# DC309A_TXOUT.net
KiCad netlist of a schematic drawn in Altium Designer
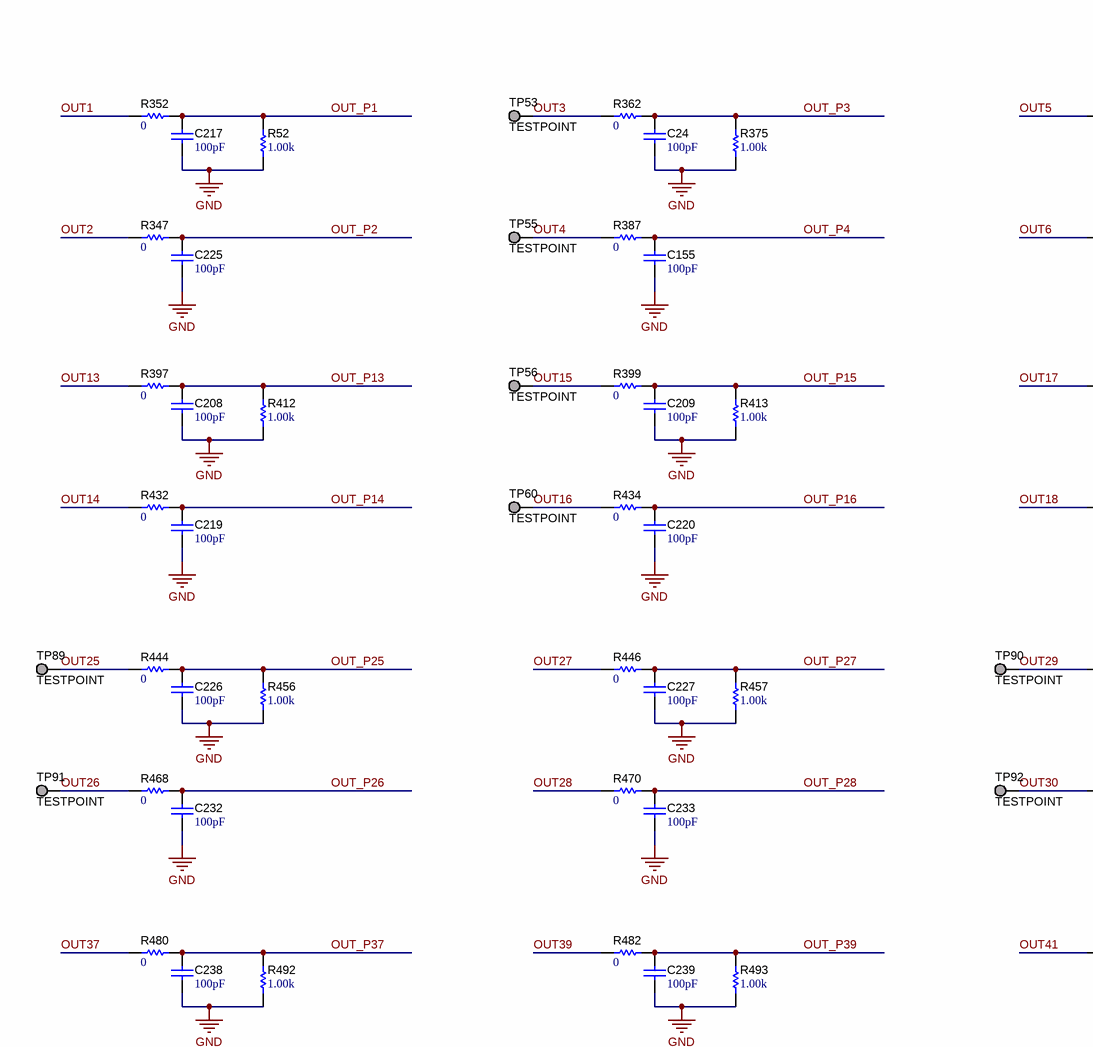
[diagram p0: DC309A_TXOUT.SchDoc, top left]
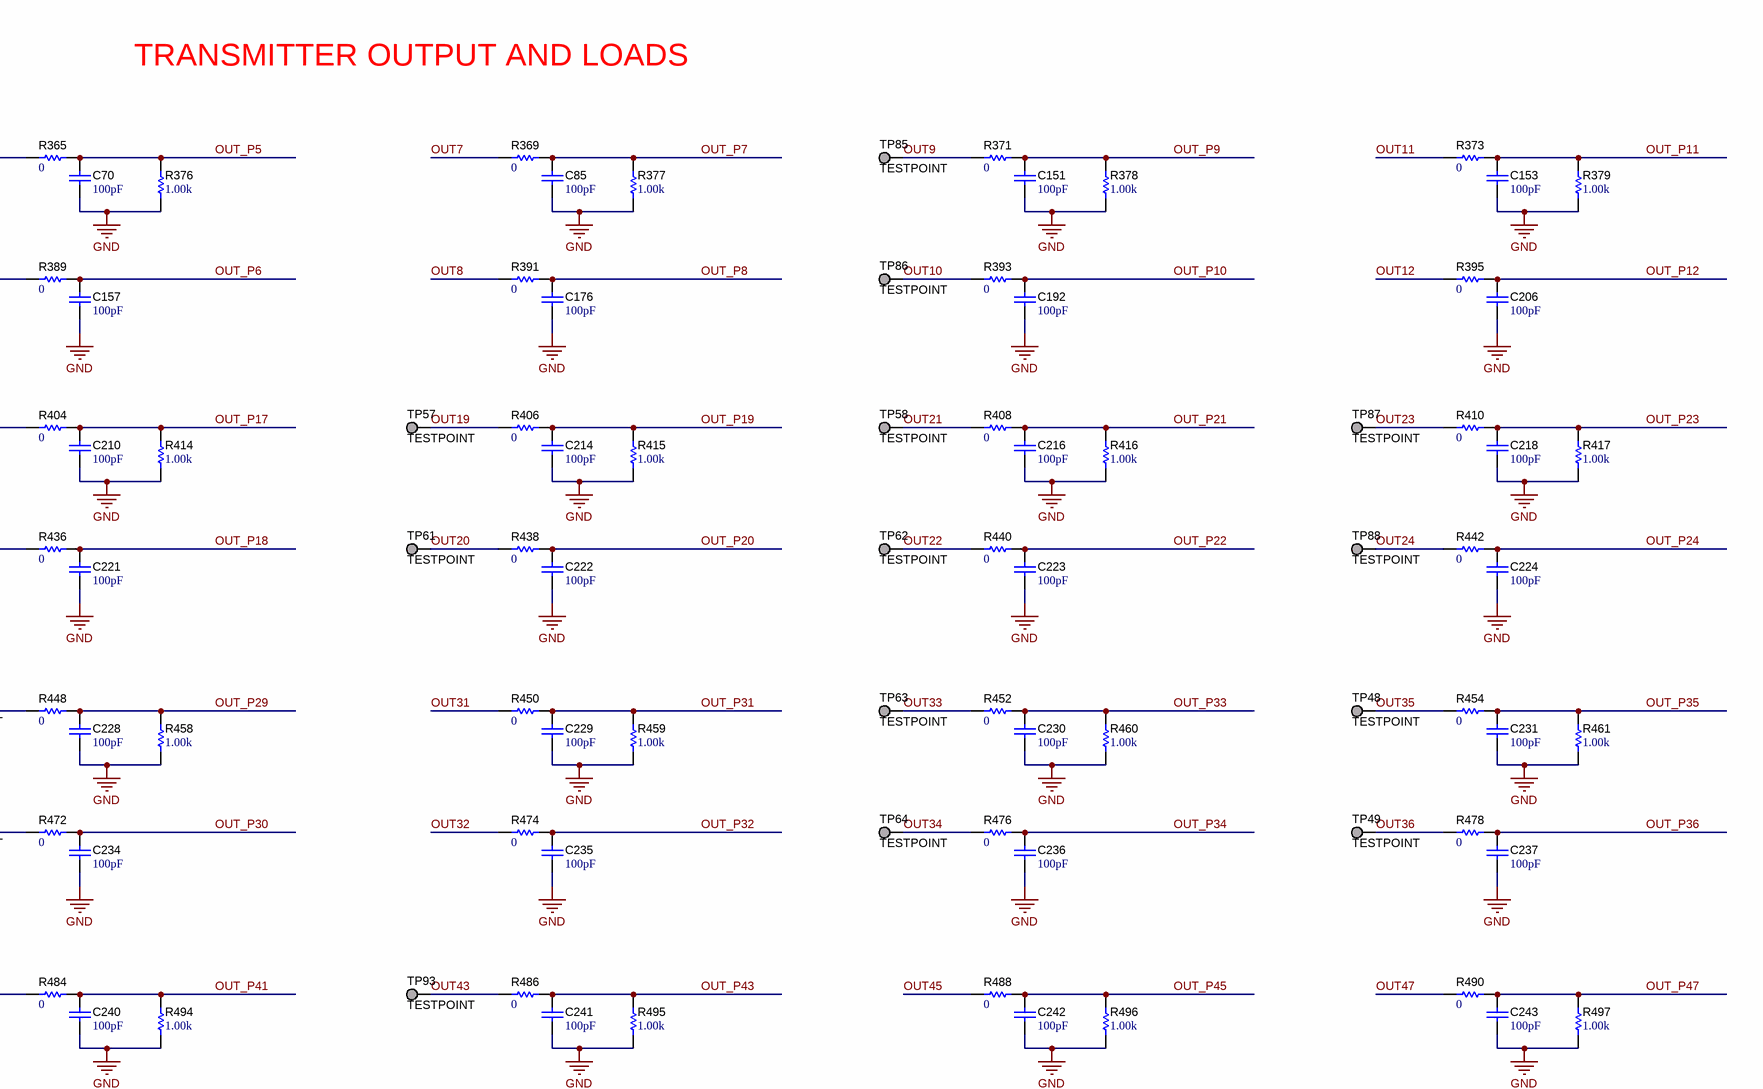
[diagram p1: DC309A_TXOUT.SchDoc, top right]
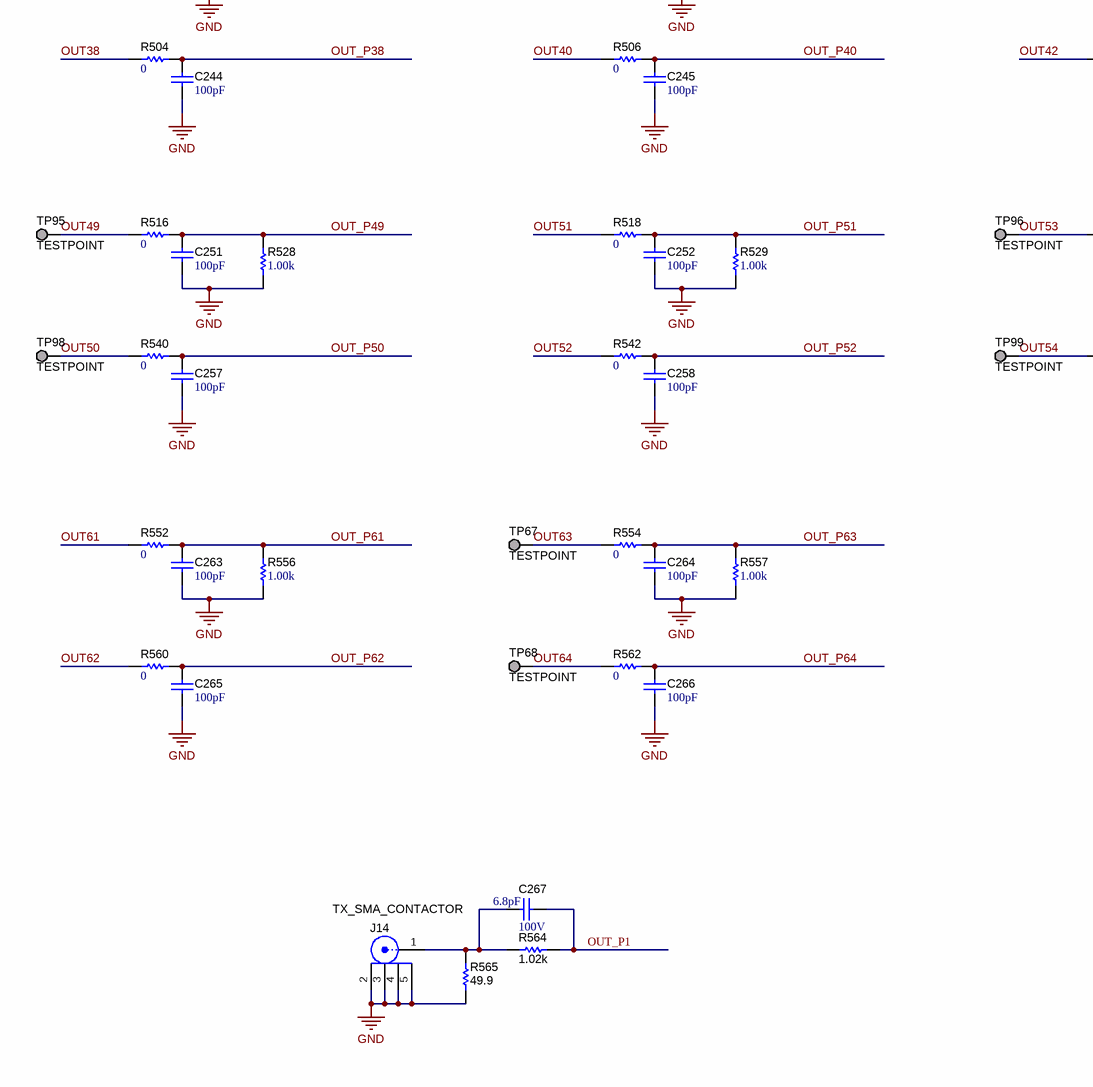
[diagram p2: DC309A_TXOUT.SchDoc, bottom left]
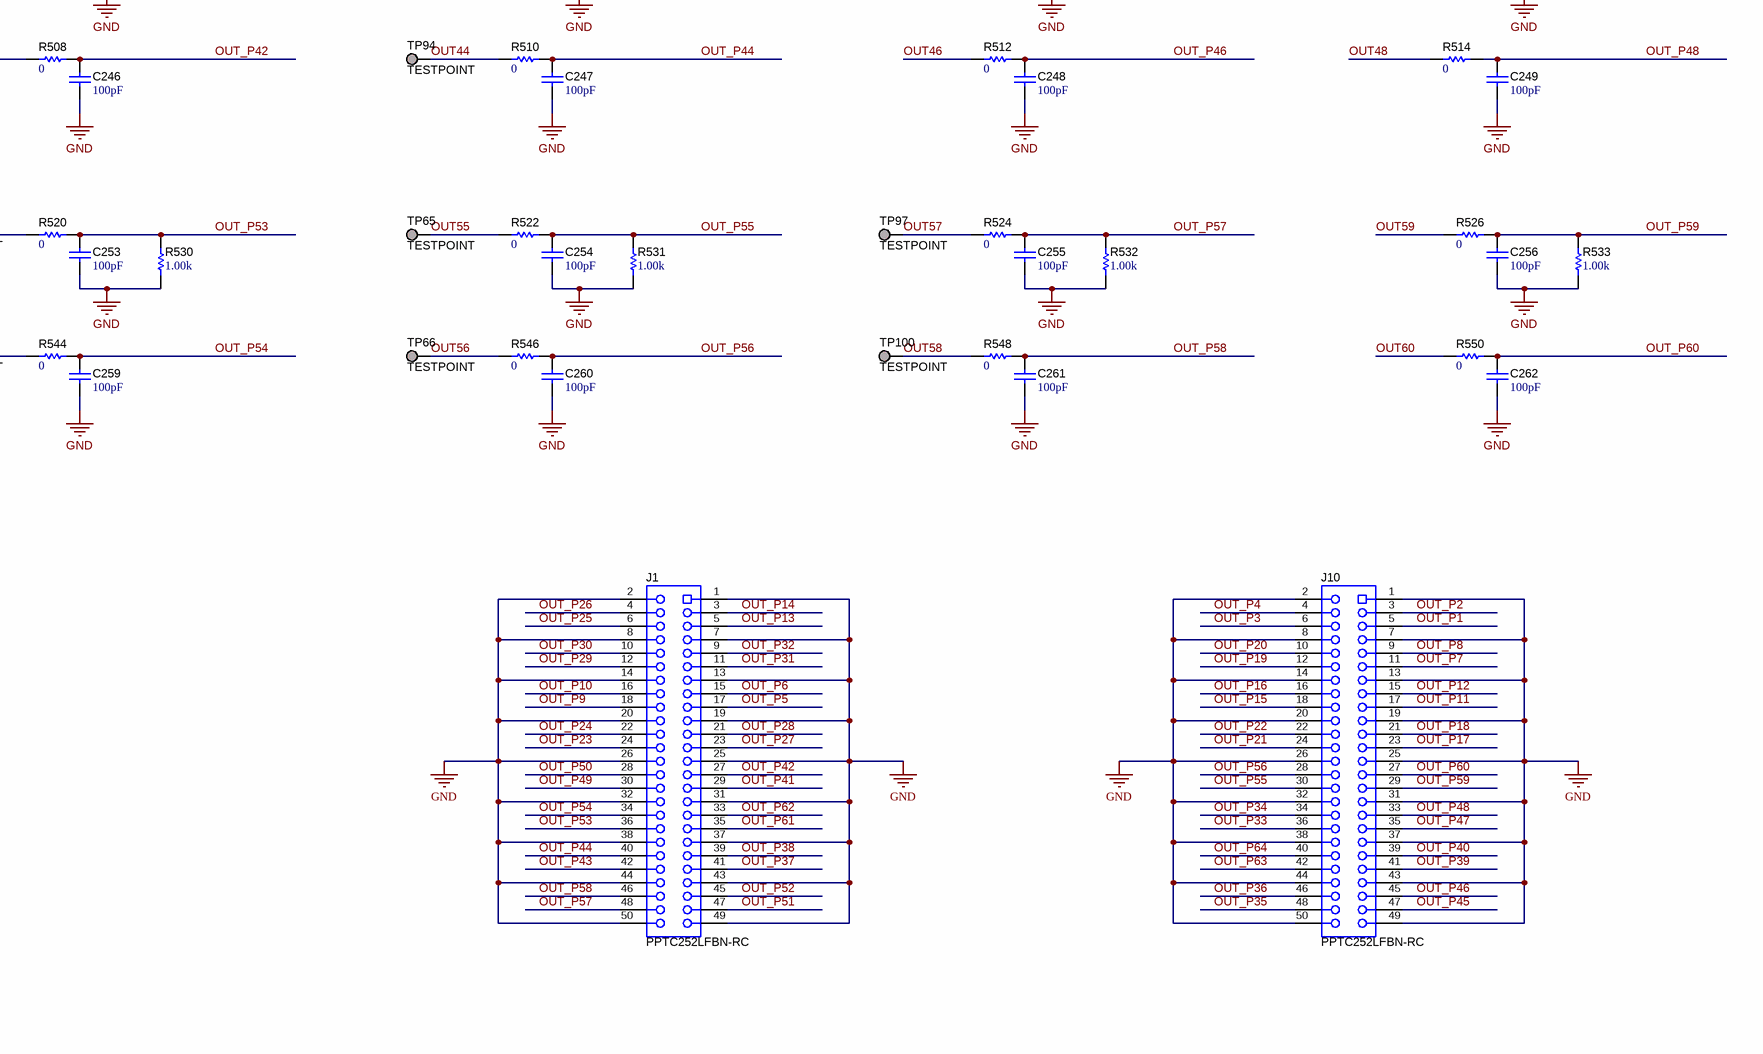
[diagram p3: DC309A_TXOUT.SchDoc, bottom right]

(export (version "E")
  (design (tool "Eeschema 10.0.6"))
  (components
    (comp (ref "C24")
      (value "AC0603JRNPOYBN101")
      (footprint "0603")
      (description "CAP, CERM, 100 pF, 250 V,+/- 5%, C0G/NP0, AEC-Q200 Grade 1, 0603")
      (fields (field (name "VALUEDISPLAYED") "100pF") (field (name "MANUFACTURER") "Yageo"))
      (libsource (lib "Altium Vault - TI") (part "Capacitor"))
    )
    (comp (ref "C70")
      (value "AC0603JRNPOYBN101")
      (footprint "0603")
      (description "CAP, CERM, 100 pF, 250 V,+/- 5%, C0G/NP0, AEC-Q200 Grade 1, 0603")
      (fields (field (name "VALUEDISPLAYED") "100pF") (field (name "MANUFACTURER") "Yageo"))
      (libsource (lib "Altium Vault - TI") (part "Capacitor"))
    )
    (comp (ref "C85")
      (value "AC0603JRNPOYBN101")
      (footprint "0603")
      (description "CAP, CERM, 100 pF, 250 V,+/- 5%, C0G/NP0, AEC-Q200 Grade 1, 0603")
      (fields (field (name "VALUEDISPLAYED") "100pF") (field (name "MANUFACTURER") "Yageo"))
      (libsource (lib "Altium Vault - TI") (part "Capacitor"))
    )
    (comp (ref "C151")
      (value "AC0603JRNPOYBN101")
      (footprint "0603")
      (description "CAP, CERM, 100 pF, 250 V,+/- 5%, C0G/NP0, AEC-Q200 Grade 1, 0603")
      (fields (field (name "VALUEDISPLAYED") "100pF") (field (name "MANUFACTURER") "Yageo"))
      (libsource (lib "Altium Vault - TI") (part "Capacitor"))
    )
    (comp (ref "C153")
      (value "AC0603JRNPOYBN101")
      (footprint "0603")
      (description "CAP, CERM, 100 pF, 250 V,+/- 5%, C0G/NP0, AEC-Q200 Grade 1, 0603")
      (fields (field (name "VALUEDISPLAYED") "100pF") (field (name "MANUFACTURER") "Yageo"))
      (libsource (lib "Altium Vault - TI") (part "Capacitor"))
    )
    (comp (ref "C155")
      (value "AC0603JRNPOYBN101")
      (footprint "0603")
      (description "CAP, CERM, 100 pF, 250 V,+/- 5%, C0G/NP0, AEC-Q200 Grade 1, 0603")
      (fields (field (name "VALUEDISPLAYED") "100pF") (field (name "MANUFACTURER") "Yageo"))
      (libsource (lib "Altium Vault - TI") (part "Capacitor"))
    )
    (comp (ref "C157")
      (value "AC0603JRNPOYBN101")
      (footprint "0603")
      (description "CAP, CERM, 100 pF, 250 V,+/- 5%, C0G/NP0, AEC-Q200 Grade 1, 0603")
      (fields (field (name "VALUEDISPLAYED") "100pF") (field (name "MANUFACTURER") "Yageo"))
      (libsource (lib "Altium Vault - TI") (part "Capacitor"))
    )
    (comp (ref "C176")
      (value "AC0603JRNPOYBN101")
      (footprint "0603")
      (description "CAP, CERM, 100 pF, 250 V,+/- 5%, C0G/NP0, AEC-Q200 Grade 1, 0603")
      (fields (field (name "VALUEDISPLAYED") "100pF") (field (name "MANUFACTURER") "Yageo"))
      (libsource (lib "Altium Vault - TI") (part "Capacitor"))
    )
    (comp (ref "C192")
      (value "AC0603JRNPOYBN101")
      (footprint "0603")
      (description "CAP, CERM, 100 pF, 250 V,+/- 5%, C0G/NP0, AEC-Q200 Grade 1, 0603")
      (fields (field (name "VALUEDISPLAYED") "100pF") (field (name "MANUFACTURER") "Yageo"))
      (libsource (lib "Altium Vault - TI") (part "Capacitor"))
    )
    (comp (ref "C206")
      (value "AC0603JRNPOYBN101")
      (footprint "0603")
      (description "CAP, CERM, 100 pF, 250 V,+/- 5%, C0G/NP0, AEC-Q200 Grade 1, 0603")
      (fields (field (name "VALUEDISPLAYED") "100pF") (field (name "MANUFACTURER") "Yageo"))
      (libsource (lib "Altium Vault - TI") (part "Capacitor"))
    )
    (comp (ref "C208")
      (value "AC0603JRNPOYBN101")
      (footprint "0603")
      (description "CAP, CERM, 100 pF, 250 V,+/- 5%, C0G/NP0, AEC-Q200 Grade 1, 0603")
      (fields (field (name "VALUEDISPLAYED") "100pF") (field (name "MANUFACTURER") "Yageo"))
      (libsource (lib "Altium Vault - TI") (part "Capacitor"))
    )
    (comp (ref "C209")
      (value "AC0603JRNPOYBN101")
      (footprint "0603")
      (description "CAP, CERM, 100 pF, 250 V,+/- 5%, C0G/NP0, AEC-Q200 Grade 1, 0603")
      (fields (field (name "VALUEDISPLAYED") "100pF") (field (name "MANUFACTURER") "Yageo"))
      (libsource (lib "Altium Vault - TI") (part "Capacitor"))
    )
    (comp (ref "C210")
      (value "AC0603JRNPOYBN101")
      (footprint "0603")
      (description "CAP, CERM, 100 pF, 250 V,+/- 5%, C0G/NP0, AEC-Q200 Grade 1, 0603")
      (fields (field (name "VALUEDISPLAYED") "100pF") (field (name "MANUFACTURER") "Yageo"))
      (libsource (lib "Altium Vault - TI") (part "Capacitor"))
    )
    (comp (ref "C214")
      (value "AC0603JRNPOYBN101")
      (footprint "0603")
      (description "CAP, CERM, 100 pF, 250 V,+/- 5%, C0G/NP0, AEC-Q200 Grade 1, 0603")
      (fields (field (name "VALUEDISPLAYED") "100pF") (field (name "MANUFACTURER") "Yageo"))
      (libsource (lib "Altium Vault - TI") (part "Capacitor"))
    )
    (comp (ref "C216")
      (value "AC0603JRNPOYBN101")
      (footprint "0603")
      (description "CAP, CERM, 100 pF, 250 V,+/- 5%, C0G/NP0, AEC-Q200 Grade 1, 0603")
      (fields (field (name "VALUEDISPLAYED") "100pF") (field (name "MANUFACTURER") "Yageo"))
      (libsource (lib "Altium Vault - TI") (part "Capacitor"))
    )
    (comp (ref "C217")
      (value "AC0603JRNPOYBN101")
      (footprint "0603")
      (description "CAP, CERM, 100 pF, 250 V,+/- 5%, C0G/NP0, AEC-Q200 Grade 1, 0603")
      (fields (field (name "VALUEDISPLAYED") "100pF") (field (name "MANUFACTURER") "Yageo"))
      (libsource (lib "Altium Vault - TI") (part "Capacitor"))
    )
    (comp (ref "C218")
      (value "AC0603JRNPOYBN101")
      (footprint "0603")
      (description "CAP, CERM, 100 pF, 250 V,+/- 5%, C0G/NP0, AEC-Q200 Grade 1, 0603")
      (fields (field (name "VALUEDISPLAYED") "100pF") (field (name "MANUFACTURER") "Yageo"))
      (libsource (lib "Altium Vault - TI") (part "Capacitor"))
    )
    (comp (ref "C219")
      (value "AC0603JRNPOYBN101")
      (footprint "0603")
      (description "CAP, CERM, 100 pF, 250 V,+/- 5%, C0G/NP0, AEC-Q200 Grade 1, 0603")
      (fields (field (name "VALUEDISPLAYED") "100pF") (field (name "MANUFACTURER") "Yageo"))
      (libsource (lib "Altium Vault - TI") (part "Capacitor"))
    )
    (comp (ref "C220")
      (value "AC0603JRNPOYBN101")
      (footprint "0603")
      (description "CAP, CERM, 100 pF, 250 V,+/- 5%, C0G/NP0, AEC-Q200 Grade 1, 0603")
      (fields (field (name "VALUEDISPLAYED") "100pF") (field (name "MANUFACTURER") "Yageo"))
      (libsource (lib "Altium Vault - TI") (part "Capacitor"))
    )
    (comp (ref "C221")
      (value "AC0603JRNPOYBN101")
      (footprint "0603")
      (description "CAP, CERM, 100 pF, 250 V,+/- 5%, C0G/NP0, AEC-Q200 Grade 1, 0603")
      (fields (field (name "VALUEDISPLAYED") "100pF") (field (name "MANUFACTURER") "Yageo"))
      (libsource (lib "Altium Vault - TI") (part "Capacitor"))
    )
    (comp (ref "C222")
      (value "AC0603JRNPOYBN101")
      (footprint "0603")
      (description "CAP, CERM, 100 pF, 250 V,+/- 5%, C0G/NP0, AEC-Q200 Grade 1, 0603")
      (fields (field (name "VALUEDISPLAYED") "100pF") (field (name "MANUFACTURER") "Yageo"))
      (libsource (lib "Altium Vault - TI") (part "Capacitor"))
    )
    (comp (ref "C223")
      (value "AC0603JRNPOYBN101")
      (footprint "0603")
      (description "CAP, CERM, 100 pF, 250 V,+/- 5%, C0G/NP0, AEC-Q200 Grade 1, 0603")
      (fields (field (name "VALUEDISPLAYED") "100pF") (field (name "MANUFACTURER") "Yageo"))
      (libsource (lib "Altium Vault - TI") (part "Capacitor"))
    )
    (comp (ref "C224")
      (value "AC0603JRNPOYBN101")
      (footprint "0603")
      (description "CAP, CERM, 100 pF, 250 V,+/- 5%, C0G/NP0, AEC-Q200 Grade 1, 0603")
      (fields (field (name "VALUEDISPLAYED") "100pF") (field (name "MANUFACTURER") "Yageo"))
      (libsource (lib "Altium Vault - TI") (part "Capacitor"))
    )
    (comp (ref "C225")
      (value "AC0603JRNPOYBN101")
      (footprint "0603")
      (description "CAP, CERM, 100 pF, 250 V,+/- 5%, C0G/NP0, AEC-Q200 Grade 1, 0603")
      (fields (field (name "VALUEDISPLAYED") "100pF") (field (name "MANUFACTURER") "Yageo"))
      (libsource (lib "Altium Vault - TI") (part "Capacitor"))
    )
    (comp (ref "C226")
      (value "AC0603JRNPOYBN101")
      (footprint "0603")
      (description "CAP, CERM, 100 pF, 250 V,+/- 5%, C0G/NP0, AEC-Q200 Grade 1, 0603")
      (fields (field (name "VALUEDISPLAYED") "100pF") (field (name "MANUFACTURER") "Yageo"))
      (libsource (lib "Altium Vault - TI") (part "Capacitor"))
    )
    (comp (ref "C227")
      (value "AC0603JRNPOYBN101")
      (footprint "0603")
      (description "CAP, CERM, 100 pF, 250 V,+/- 5%, C0G/NP0, AEC-Q200 Grade 1, 0603")
      (fields (field (name "VALUEDISPLAYED") "100pF") (field (name "MANUFACTURER") "Yageo"))
      (libsource (lib "Altium Vault - TI") (part "Capacitor"))
    )
    (comp (ref "C228")
      (value "AC0603JRNPOYBN101")
      (footprint "0603")
      (description "CAP, CERM, 100 pF, 250 V,+/- 5%, C0G/NP0, AEC-Q200 Grade 1, 0603")
      (fields (field (name "VALUEDISPLAYED") "100pF") (field (name "MANUFACTURER") "Yageo"))
      (libsource (lib "Altium Vault - TI") (part "Capacitor"))
    )
    (comp (ref "C229")
      (value "AC0603JRNPOYBN101")
      (footprint "0603")
      (description "CAP, CERM, 100 pF, 250 V,+/- 5%, C0G/NP0, AEC-Q200 Grade 1, 0603")
      (fields (field (name "VALUEDISPLAYED") "100pF") (field (name "MANUFACTURER") "Yageo"))
      (libsource (lib "Altium Vault - TI") (part "Capacitor"))
    )
    (comp (ref "C230")
      (value "AC0603JRNPOYBN101")
      (footprint "0603")
      (description "CAP, CERM, 100 pF, 250 V,+/- 5%, C0G/NP0, AEC-Q200 Grade 1, 0603")
      (fields (field (name "VALUEDISPLAYED") "100pF") (field (name "MANUFACTURER") "Yageo"))
      (libsource (lib "Altium Vault - TI") (part "Capacitor"))
    )
    (comp (ref "C231")
      (value "AC0603JRNPOYBN101")
      (footprint "0603")
      (description "CAP, CERM, 100 pF, 250 V,+/- 5%, C0G/NP0, AEC-Q200 Grade 1, 0603")
      (fields (field (name "VALUEDISPLAYED") "100pF") (field (name "MANUFACTURER") "Yageo"))
      (libsource (lib "Altium Vault - TI") (part "Capacitor"))
    )
    (comp (ref "C232")
      (value "AC0603JRNPOYBN101")
      (footprint "0603")
      (description "CAP, CERM, 100 pF, 250 V,+/- 5%, C0G/NP0, AEC-Q200 Grade 1, 0603")
      (fields (field (name "VALUEDISPLAYED") "100pF") (field (name "MANUFACTURER") "Yageo"))
      (libsource (lib "Altium Vault - TI") (part "Capacitor"))
    )
    (comp (ref "C233")
      (value "AC0603JRNPOYBN101")
      (footprint "0603")
      (description "CAP, CERM, 100 pF, 250 V,+/- 5%, C0G/NP0, AEC-Q200 Grade 1, 0603")
      (fields (field (name "VALUEDISPLAYED") "100pF") (field (name "MANUFACTURER") "Yageo"))
      (libsource (lib "Altium Vault - TI") (part "Capacitor"))
    )
    (comp (ref "C234")
      (value "AC0603JRNPOYBN101")
      (footprint "0603")
      (description "CAP, CERM, 100 pF, 250 V,+/- 5%, C0G/NP0, AEC-Q200 Grade 1, 0603")
      (fields (field (name "VALUEDISPLAYED") "100pF") (field (name "MANUFACTURER") "Yageo"))
      (libsource (lib "Altium Vault - TI") (part "Capacitor"))
    )
    (comp (ref "C235")
      (value "AC0603JRNPOYBN101")
      (footprint "0603")
      (description "CAP, CERM, 100 pF, 250 V,+/- 5%, C0G/NP0, AEC-Q200 Grade 1, 0603")
      (fields (field (name "VALUEDISPLAYED") "100pF") (field (name "MANUFACTURER") "Yageo"))
      (libsource (lib "Altium Vault - TI") (part "Capacitor"))
    )
    (comp (ref "C236")
      (value "AC0603JRNPOYBN101")
      (footprint "0603")
      (description "CAP, CERM, 100 pF, 250 V,+/- 5%, C0G/NP0, AEC-Q200 Grade 1, 0603")
      (fields (field (name "VALUEDISPLAYED") "100pF") (field (name "MANUFACTURER") "Yageo"))
      (libsource (lib "Altium Vault - TI") (part "Capacitor"))
    )
    (comp (ref "C237")
      (value "AC0603JRNPOYBN101")
      (footprint "0603")
      (description "CAP, CERM, 100 pF, 250 V,+/- 5%, C0G/NP0, AEC-Q200 Grade 1, 0603")
      (fields (field (name "VALUEDISPLAYED") "100pF") (field (name "MANUFACTURER") "Yageo"))
      (libsource (lib "Altium Vault - TI") (part "Capacitor"))
    )
    (comp (ref "C238")
      (value "AC0603JRNPOYBN101")
      (footprint "0603")
      (description "CAP, CERM, 100 pF, 250 V,+/- 5%, C0G/NP0, AEC-Q200 Grade 1, 0603")
      (fields (field (name "VALUEDISPLAYED") "100pF") (field (name "MANUFACTURER") "Yageo"))
      (libsource (lib "Altium Vault - TI") (part "Capacitor"))
    )
    (comp (ref "C239")
      (value "AC0603JRNPOYBN101")
      (footprint "0603")
      (description "CAP, CERM, 100 pF, 250 V,+/- 5%, C0G/NP0, AEC-Q200 Grade 1, 0603")
      (fields (field (name "VALUEDISPLAYED") "100pF") (field (name "MANUFACTURER") "Yageo"))
      (libsource (lib "Altium Vault - TI") (part "Capacitor"))
    )
    (comp (ref "C240")
      (value "AC0603JRNPOYBN101")
      (footprint "0603")
      (description "CAP, CERM, 100 pF, 250 V,+/- 5%, C0G/NP0, AEC-Q200 Grade 1, 0603")
      (fields (field (name "VALUEDISPLAYED") "100pF") (field (name "MANUFACTURER") "Yageo"))
      (libsource (lib "Altium Vault - TI") (part "Capacitor"))
    )
    (comp (ref "C241")
      (value "AC0603JRNPOYBN101")
      (footprint "0603")
      (description "CAP, CERM, 100 pF, 250 V,+/- 5%, C0G/NP0, AEC-Q200 Grade 1, 0603")
      (fields (field (name "VALUEDISPLAYED") "100pF") (field (name "MANUFACTURER") "Yageo"))
      (libsource (lib "Altium Vault - TI") (part "Capacitor"))
    )
    (comp (ref "C242")
      (value "AC0603JRNPOYBN101")
      (footprint "0603")
      (description "CAP, CERM, 100 pF, 250 V,+/- 5%, C0G/NP0, AEC-Q200 Grade 1, 0603")
      (fields (field (name "VALUEDISPLAYED") "100pF") (field (name "MANUFACTURER") "Yageo"))
      (libsource (lib "Altium Vault - TI") (part "Capacitor"))
    )
    (comp (ref "C243")
      (value "AC0603JRNPOYBN101")
      (footprint "0603")
      (description "CAP, CERM, 100 pF, 250 V,+/- 5%, C0G/NP0, AEC-Q200 Grade 1, 0603")
      (fields (field (name "VALUEDISPLAYED") "100pF") (field (name "MANUFACTURER") "Yageo"))
      (libsource (lib "Altium Vault - TI") (part "Capacitor"))
    )
    (comp (ref "C244")
      (value "AC0603JRNPOYBN101")
      (footprint "0603")
      (description "CAP, CERM, 100 pF, 250 V,+/- 5%, C0G/NP0, AEC-Q200 Grade 1, 0603")
      (fields (field (name "VALUEDISPLAYED") "100pF") (field (name "MANUFACTURER") "Yageo"))
      (libsource (lib "Altium Vault - TI") (part "Capacitor"))
    )
    (comp (ref "C245")
      (value "AC0603JRNPOYBN101")
      (footprint "0603")
      (description "CAP, CERM, 100 pF, 250 V,+/- 5%, C0G/NP0, AEC-Q200 Grade 1, 0603")
      (fields (field (name "VALUEDISPLAYED") "100pF") (field (name "MANUFACTURER") "Yageo"))
      (libsource (lib "Altium Vault - TI") (part "Capacitor"))
    )
    (comp (ref "C246")
      (value "AC0603JRNPOYBN101")
      (footprint "0603")
      (description "CAP, CERM, 100 pF, 250 V,+/- 5%, C0G/NP0, AEC-Q200 Grade 1, 0603")
      (fields (field (name "VALUEDISPLAYED") "100pF") (field (name "MANUFACTURER") "Yageo"))
      (libsource (lib "Altium Vault - TI") (part "Capacitor"))
    )
    (comp (ref "C247")
      (value "AC0603JRNPOYBN101")
      (footprint "0603")
      (description "CAP, CERM, 100 pF, 250 V,+/- 5%, C0G/NP0, AEC-Q200 Grade 1, 0603")
      (fields (field (name "VALUEDISPLAYED") "100pF") (field (name "MANUFACTURER") "Yageo"))
      (libsource (lib "Altium Vault - TI") (part "Capacitor"))
    )
    (comp (ref "C248")
      (value "AC0603JRNPOYBN101")
      (footprint "0603")
      (description "CAP, CERM, 100 pF, 250 V,+/- 5%, C0G/NP0, AEC-Q200 Grade 1, 0603")
      (fields (field (name "VALUEDISPLAYED") "100pF") (field (name "MANUFACTURER") "Yageo"))
      (libsource (lib "Altium Vault - TI") (part "Capacitor"))
    )
    (comp (ref "C249")
      (value "AC0603JRNPOYBN101")
      (footprint "0603")
      (description "CAP, CERM, 100 pF, 250 V,+/- 5%, C0G/NP0, AEC-Q200 Grade 1, 0603")
      (fields (field (name "VALUEDISPLAYED") "100pF") (field (name "MANUFACTURER") "Yageo"))
      (libsource (lib "Altium Vault - TI") (part "Capacitor"))
    )
    (comp (ref "C251")
      (value "AC0603JRNPOYBN101")
      (footprint "0603")
      (description "CAP, CERM, 100 pF, 250 V,+/- 5%, C0G/NP0, AEC-Q200 Grade 1, 0603")
      (fields (field (name "VALUEDISPLAYED") "100pF") (field (name "MANUFACTURER") "Yageo"))
      (libsource (lib "Altium Vault - TI") (part "Capacitor"))
    )
    (comp (ref "C252")
      (value "AC0603JRNPOYBN101")
      (footprint "0603")
      (description "CAP, CERM, 100 pF, 250 V,+/- 5%, C0G/NP0, AEC-Q200 Grade 1, 0603")
      (fields (field (name "VALUEDISPLAYED") "100pF") (field (name "MANUFACTURER") "Yageo"))
      (libsource (lib "Altium Vault - TI") (part "Capacitor"))
    )
    (comp (ref "C253")
      (value "AC0603JRNPOYBN101")
      (footprint "0603")
      (description "CAP, CERM, 100 pF, 250 V,+/- 5%, C0G/NP0, AEC-Q200 Grade 1, 0603")
      (fields (field (name "VALUEDISPLAYED") "100pF") (field (name "MANUFACTURER") "Yageo"))
      (libsource (lib "Altium Vault - TI") (part "Capacitor"))
    )
    (comp (ref "C254")
      (value "AC0603JRNPOYBN101")
      (footprint "0603")
      (description "CAP, CERM, 100 pF, 250 V,+/- 5%, C0G/NP0, AEC-Q200 Grade 1, 0603")
      (fields (field (name "VALUEDISPLAYED") "100pF") (field (name "MANUFACTURER") "Yageo"))
      (libsource (lib "Altium Vault - TI") (part "Capacitor"))
    )
    (comp (ref "C255")
      (value "AC0603JRNPOYBN101")
      (footprint "0603")
      (description "CAP, CERM, 100 pF, 250 V,+/- 5%, C0G/NP0, AEC-Q200 Grade 1, 0603")
      (fields (field (name "VALUEDISPLAYED") "100pF") (field (name "MANUFACTURER") "Yageo"))
      (libsource (lib "Altium Vault - TI") (part "Capacitor"))
    )
    (comp (ref "C256")
      (value "AC0603JRNPOYBN101")
      (footprint "0603")
      (description "CAP, CERM, 100 pF, 250 V,+/- 5%, C0G/NP0, AEC-Q200 Grade 1, 0603")
      (fields (field (name "VALUEDISPLAYED") "100pF") (field (name "MANUFACTURER") "Yageo"))
      (libsource (lib "Altium Vault - TI") (part "Capacitor"))
    )
    (comp (ref "C257")
      (value "AC0603JRNPOYBN101")
      (footprint "0603")
      (description "CAP, CERM, 100 pF, 250 V,+/- 5%, C0G/NP0, AEC-Q200 Grade 1, 0603")
      (fields (field (name "VALUEDISPLAYED") "100pF") (field (name "MANUFACTURER") "Yageo"))
      (libsource (lib "Altium Vault - TI") (part "Capacitor"))
    )
    (comp (ref "C258")
      (value "AC0603JRNPOYBN101")
      (footprint "0603")
      (description "CAP, CERM, 100 pF, 250 V,+/- 5%, C0G/NP0, AEC-Q200 Grade 1, 0603")
      (fields (field (name "VALUEDISPLAYED") "100pF") (field (name "MANUFACTURER") "Yageo"))
      (libsource (lib "Altium Vault - TI") (part "Capacitor"))
    )
    (comp (ref "C259")
      (value "AC0603JRNPOYBN101")
      (footprint "0603")
      (description "CAP, CERM, 100 pF, 250 V,+/- 5%, C0G/NP0, AEC-Q200 Grade 1, 0603")
      (fields (field (name "VALUEDISPLAYED") "100pF") (field (name "MANUFACTURER") "Yageo"))
      (libsource (lib "Altium Vault - TI") (part "Capacitor"))
    )
    (comp (ref "C260")
      (value "AC0603JRNPOYBN101")
      (footprint "0603")
      (description "CAP, CERM, 100 pF, 250 V,+/- 5%, C0G/NP0, AEC-Q200 Grade 1, 0603")
      (fields (field (name "VALUEDISPLAYED") "100pF") (field (name "MANUFACTURER") "Yageo"))
      (libsource (lib "Altium Vault - TI") (part "Capacitor"))
    )
    (comp (ref "C261")
      (value "AC0603JRNPOYBN101")
      (footprint "0603")
      (description "CAP, CERM, 100 pF, 250 V,+/- 5%, C0G/NP0, AEC-Q200 Grade 1, 0603")
      (fields (field (name "VALUEDISPLAYED") "100pF") (field (name "MANUFACTURER") "Yageo"))
      (libsource (lib "Altium Vault - TI") (part "Capacitor"))
    )
    (comp (ref "C262")
      (value "AC0603JRNPOYBN101")
      (footprint "0603")
      (description "CAP, CERM, 100 pF, 250 V,+/- 5%, C0G/NP0, AEC-Q200 Grade 1, 0603")
      (fields (field (name "VALUEDISPLAYED") "100pF") (field (name "MANUFACTURER") "Yageo"))
      (libsource (lib "Altium Vault - TI") (part "Capacitor"))
    )
    (comp (ref "C263")
      (value "AC0603JRNPOYBN101")
      (footprint "0603")
      (description "CAP, CERM, 100 pF, 250 V,+/- 5%, C0G/NP0, AEC-Q200 Grade 1, 0603")
      (fields (field (name "VALUEDISPLAYED") "100pF") (field (name "MANUFACTURER") "Yageo"))
      (libsource (lib "Altium Vault - TI") (part "Capacitor"))
    )
    (comp (ref "C264")
      (value "AC0603JRNPOYBN101")
      (footprint "0603")
      (description "CAP, CERM, 100 pF, 250 V,+/- 5%, C0G/NP0, AEC-Q200 Grade 1, 0603")
      (fields (field (name "VALUEDISPLAYED") "100pF") (field (name "MANUFACTURER") "Yageo"))
      (libsource (lib "Altium Vault - TI") (part "Capacitor"))
    )
    (comp (ref "C265")
      (value "AC0603JRNPOYBN101")
      (footprint "0603")
      (description "CAP, CERM, 100 pF, 250 V,+/- 5%, C0G/NP0, AEC-Q200 Grade 1, 0603")
      (fields (field (name "VALUEDISPLAYED") "100pF") (field (name "MANUFACTURER") "Yageo"))
      (libsource (lib "Altium Vault - TI") (part "Capacitor"))
    )
    (comp (ref "C266")
      (value "AC0603JRNPOYBN101")
      (footprint "0603")
      (description "CAP, CERM, 100 pF, 250 V,+/- 5%, C0G/NP0, AEC-Q200 Grade 1, 0603")
      (fields (field (name "VALUEDISPLAYED") "100pF") (field (name "MANUFACTURER") "Yageo"))
      (libsource (lib "Altium Vault - TI") (part "Capacitor"))
    )
    (comp (ref "C267")
      (value "CC0603CRNPO0BN6R8")
      (footprint "0603")
      (description "CAP, CERM, 6.8 pF, 100 V,+/- 3.7%, C0G/NP0, 0603")
      (fields
        (field (name "MANUFACTURER") "Yageo")
        (field (name "VDC_V") "100V")
        (field (name "VALUEDISPLAYED") "6.8pF")
      )
      (libsource (lib "Altium Vault - TI") (part "Capacitor"))
    )
    (comp (ref "J1")
      (value "PPTC252LFBN-RC")
      (footprint "Sullins_xPxC252LFBN")
      (description "Receptacle, 2.54mm, 25x2, Tin, TH")
      (fields
        (field (name "MANUFACTURER") "Sullins Connector Solutions")
        (field (name "PUBLISHER") "Texas Instruments")
      )
      (libsource (lib "Altium Vault - TI") (part "Receptacle_25x2"))
    )
    (comp (ref "J10")
      (value "PPTC252LFBN-RC")
      (footprint "Sullins_xPxC252LFBN")
      (description "Receptacle, 2.54mm, 25x2, Tin, TH")
      (fields
        (field (name "MANUFACTURER") "Sullins Connector Solutions")
        (field (name "PUBLISHER") "Texas Instruments")
      )
      (libsource (lib "Altium Vault - TI") (part "Receptacle_25x2"))
    )
    (comp (ref "J14")
      (value "901-144-8RFX")
      (footprint "AMPHENOL_901-144-8RFX")
      (description "SMA Straight Jack, Gold, 50 Ohm, TH")
      (fields (field (name "MANUFACTURER") "Amphenol RF") (field (name "PUBLISHER") "Texas Instruments"))
      (libsource (lib "Altium Vault - TI") (part "SMA_Contact1_GND2345"))
    )
    (comp (ref "R52")
      (value "CRCW25121K00FKEG")
      (footprint "2512")
      (description "RES, 1.00 k, 1%, 1 W, AEC-Q200 Grade 0, 2512")
      (fields (field (name "MANUFACTURER") "Vishay-Dale") (field (name "VALUEDISPLAYED") "1.00k"))
      (libsource (lib "Altium Vault - TI") (part "Resistor"))
    )
    (comp (ref "R347")
      (value "5106")
      (footprint "5106")
      (description "RES, 0, 1%, 0.5 W, 0805")
      (fields
        (field (name "MANUFACTURER") "Keystone")
        (field (name "VALUEDISPLAYED") "0")
        (field (name "PUBLISHER") "Texas Instruments")
      )
      (libsource (lib "Altium Vault - TI") (part "Resistor"))
    )
    (comp (ref "R352")
      (value "5106")
      (footprint "5106")
      (description "RES, 0, 1%, 0.5 W, 0805")
      (fields
        (field (name "MANUFACTURER") "Keystone")
        (field (name "VALUEDISPLAYED") "0")
        (field (name "PUBLISHER") "Texas Instruments")
      )
      (libsource (lib "Altium Vault - TI") (part "Resistor"))
    )
    (comp (ref "R362")
      (value "5106")
      (footprint "5106")
      (description "RES, 0, 1%, 0.5 W, 0805")
      (fields
        (field (name "MANUFACTURER") "Keystone")
        (field (name "VALUEDISPLAYED") "0")
        (field (name "PUBLISHER") "Texas Instruments")
      )
      (libsource (lib "Altium Vault - TI") (part "Resistor"))
    )
    (comp (ref "R365")
      (value "5106")
      (footprint "5106")
      (description "RES, 0, 1%, 0.5 W, 0805")
      (fields
        (field (name "MANUFACTURER") "Keystone")
        (field (name "VALUEDISPLAYED") "0")
        (field (name "PUBLISHER") "Texas Instruments")
      )
      (libsource (lib "Altium Vault - TI") (part "Resistor"))
    )
    (comp (ref "R369")
      (value "5106")
      (footprint "5106")
      (description "RES, 0, 1%, 0.5 W, 0805")
      (fields
        (field (name "MANUFACTURER") "Keystone")
        (field (name "VALUEDISPLAYED") "0")
        (field (name "PUBLISHER") "Texas Instruments")
      )
      (libsource (lib "Altium Vault - TI") (part "Resistor"))
    )
    (comp (ref "R371")
      (value "5106")
      (footprint "5106")
      (description "RES, 0, 1%, 0.5 W, 0805")
      (fields
        (field (name "MANUFACTURER") "Keystone")
        (field (name "VALUEDISPLAYED") "0")
        (field (name "PUBLISHER") "Texas Instruments")
      )
      (libsource (lib "Altium Vault - TI") (part "Resistor"))
    )
    (comp (ref "R373")
      (value "5106")
      (footprint "5106")
      (description "RES, 0, 1%, 0.5 W, 0805")
      (fields
        (field (name "MANUFACTURER") "Keystone")
        (field (name "VALUEDISPLAYED") "0")
        (field (name "PUBLISHER") "Texas Instruments")
      )
      (libsource (lib "Altium Vault - TI") (part "Resistor"))
    )
    (comp (ref "R375")
      (value "CRCW25121K00FKEG")
      (footprint "2512")
      (description "RES, 1.00 k, 1%, 1 W, AEC-Q200 Grade 0, 2512")
      (fields (field (name "MANUFACTURER") "Vishay-Dale") (field (name "VALUEDISPLAYED") "1.00k"))
      (libsource (lib "Altium Vault - TI") (part "Resistor"))
    )
    (comp (ref "R376")
      (value "CRCW25121K00FKEG")
      (footprint "2512")
      (description "RES, 1.00 k, 1%, 1 W, AEC-Q200 Grade 0, 2512")
      (fields (field (name "MANUFACTURER") "Vishay-Dale") (field (name "VALUEDISPLAYED") "1.00k"))
      (libsource (lib "Altium Vault - TI") (part "Resistor"))
    )
    (comp (ref "R377")
      (value "CRCW25121K00FKEG")
      (footprint "2512")
      (description "RES, 1.00 k, 1%, 1 W, AEC-Q200 Grade 0, 2512")
      (fields (field (name "MANUFACTURER") "Vishay-Dale") (field (name "VALUEDISPLAYED") "1.00k"))
      (libsource (lib "Altium Vault - TI") (part "Resistor"))
    )
    (comp (ref "R378")
      (value "CRCW25121K00FKEG")
      (footprint "2512")
      (description "RES, 1.00 k, 1%, 1 W, AEC-Q200 Grade 0, 2512")
      (fields (field (name "MANUFACTURER") "Vishay-Dale") (field (name "VALUEDISPLAYED") "1.00k"))
      (libsource (lib "Altium Vault - TI") (part "Resistor"))
    )
    (comp (ref "R379")
      (value "CRCW25121K00FKEG")
      (footprint "2512")
      (description "RES, 1.00 k, 1%, 1 W, AEC-Q200 Grade 0, 2512")
      (fields (field (name "MANUFACTURER") "Vishay-Dale") (field (name "VALUEDISPLAYED") "1.00k"))
      (libsource (lib "Altium Vault - TI") (part "Resistor"))
    )
    (comp (ref "R387")
      (value "5106")
      (footprint "5106")
      (description "RES, 0, 1%, 0.5 W, 0805")
      (fields
        (field (name "MANUFACTURER") "Keystone")
        (field (name "VALUEDISPLAYED") "0")
        (field (name "PUBLISHER") "Texas Instruments")
      )
      (libsource (lib "Altium Vault - TI") (part "Resistor"))
    )
    (comp (ref "R389")
      (value "5106")
      (footprint "5106")
      (description "RES, 0, 1%, 0.5 W, 0805")
      (fields
        (field (name "MANUFACTURER") "Keystone")
        (field (name "VALUEDISPLAYED") "0")
        (field (name "PUBLISHER") "Texas Instruments")
      )
      (libsource (lib "Altium Vault - TI") (part "Resistor"))
    )
    (comp (ref "R391")
      (value "5106")
      (footprint "5106")
      (description "RES, 0, 1%, 0.5 W, 0805")
      (fields
        (field (name "MANUFACTURER") "Keystone")
        (field (name "VALUEDISPLAYED") "0")
        (field (name "PUBLISHER") "Texas Instruments")
      )
      (libsource (lib "Altium Vault - TI") (part "Resistor"))
    )
    (comp (ref "R393")
      (value "5106")
      (footprint "5106")
      (description "RES, 0, 1%, 0.5 W, 0805")
      (fields
        (field (name "MANUFACTURER") "Keystone")
        (field (name "VALUEDISPLAYED") "0")
        (field (name "PUBLISHER") "Texas Instruments")
      )
      (libsource (lib "Altium Vault - TI") (part "Resistor"))
    )
    (comp (ref "R395")
      (value "5106")
      (footprint "5106")
      (description "RES, 0, 1%, 0.5 W, 0805")
      (fields
        (field (name "MANUFACTURER") "Keystone")
        (field (name "VALUEDISPLAYED") "0")
        (field (name "PUBLISHER") "Texas Instruments")
      )
      (libsource (lib "Altium Vault - TI") (part "Resistor"))
    )
    (comp (ref "R397")
      (value "5106")
      (footprint "5106")
      (description "RES, 0, 1%, 0.5 W, 0805")
      (fields
        (field (name "MANUFACTURER") "Keystone")
        (field (name "VALUEDISPLAYED") "0")
        (field (name "PUBLISHER") "Texas Instruments")
      )
      (libsource (lib "Altium Vault - TI") (part "Resistor"))
    )
    (comp (ref "R399")
      (value "5106")
      (footprint "5106")
      (description "RES, 0, 1%, 0.5 W, 0805")
      (fields
        (field (name "MANUFACTURER") "Keystone")
        (field (name "VALUEDISPLAYED") "0")
        (field (name "PUBLISHER") "Texas Instruments")
      )
      (libsource (lib "Altium Vault - TI") (part "Resistor"))
    )
    (comp (ref "R404")
      (value "5106")
      (footprint "5106")
      (description "RES, 0, 1%, 0.5 W, 0805")
      (fields
        (field (name "MANUFACTURER") "Keystone")
        (field (name "VALUEDISPLAYED") "0")
        (field (name "PUBLISHER") "Texas Instruments")
      )
      (libsource (lib "Altium Vault - TI") (part "Resistor"))
    )
    (comp (ref "R406")
      (value "5106")
      (footprint "5106")
      (description "RES, 0, 1%, 0.5 W, 0805")
      (fields
        (field (name "MANUFACTURER") "Keystone")
        (field (name "VALUEDISPLAYED") "0")
        (field (name "PUBLISHER") "Texas Instruments")
      )
      (libsource (lib "Altium Vault - TI") (part "Resistor"))
    )
    (comp (ref "R408")
      (value "5106")
      (footprint "5106")
      (description "RES, 0, 1%, 0.5 W, 0805")
      (fields
        (field (name "MANUFACTURER") "Keystone")
        (field (name "VALUEDISPLAYED") "0")
        (field (name "PUBLISHER") "Texas Instruments")
      )
      (libsource (lib "Altium Vault - TI") (part "Resistor"))
    )
    (comp (ref "R410")
      (value "5106")
      (footprint "5106")
      (description "RES, 0, 1%, 0.5 W, 0805")
      (fields
        (field (name "MANUFACTURER") "Keystone")
        (field (name "VALUEDISPLAYED") "0")
        (field (name "PUBLISHER") "Texas Instruments")
      )
      (libsource (lib "Altium Vault - TI") (part "Resistor"))
    )
    (comp (ref "R412")
      (value "CRCW25121K00FKEG")
      (footprint "2512")
      (description "RES, 1.00 k, 1%, 1 W, AEC-Q200 Grade 0, 2512")
      (fields (field (name "MANUFACTURER") "Vishay-Dale") (field (name "VALUEDISPLAYED") "1.00k"))
      (libsource (lib "Altium Vault - TI") (part "Resistor"))
    )
    (comp (ref "R413")
      (value "CRCW25121K00FKEG")
      (footprint "2512")
      (description "RES, 1.00 k, 1%, 1 W, AEC-Q200 Grade 0, 2512")
      (fields (field (name "MANUFACTURER") "Vishay-Dale") (field (name "VALUEDISPLAYED") "1.00k"))
      (libsource (lib "Altium Vault - TI") (part "Resistor"))
    )
    (comp (ref "R414")
      (value "CRCW25121K00FKEG")
      (footprint "2512")
      (description "RES, 1.00 k, 1%, 1 W, AEC-Q200 Grade 0, 2512")
      (fields (field (name "MANUFACTURER") "Vishay-Dale") (field (name "VALUEDISPLAYED") "1.00k"))
      (libsource (lib "Altium Vault - TI") (part "Resistor"))
    )
    (comp (ref "R415")
      (value "CRCW25121K00FKEG")
      (footprint "2512")
      (description "RES, 1.00 k, 1%, 1 W, AEC-Q200 Grade 0, 2512")
      (fields (field (name "MANUFACTURER") "Vishay-Dale") (field (name "VALUEDISPLAYED") "1.00k"))
      (libsource (lib "Altium Vault - TI") (part "Resistor"))
    )
    (comp (ref "R416")
      (value "CRCW25121K00FKEG")
      (footprint "2512")
      (description "RES, 1.00 k, 1%, 1 W, AEC-Q200 Grade 0, 2512")
      (fields (field (name "MANUFACTURER") "Vishay-Dale") (field (name "VALUEDISPLAYED") "1.00k"))
      (libsource (lib "Altium Vault - TI") (part "Resistor"))
    )
    (comp (ref "R417")
      (value "CRCW25121K00FKEG")
      (footprint "2512")
      (description "RES, 1.00 k, 1%, 1 W, AEC-Q200 Grade 0, 2512")
      (fields (field (name "MANUFACTURER") "Vishay-Dale") (field (name "VALUEDISPLAYED") "1.00k"))
      (libsource (lib "Altium Vault - TI") (part "Resistor"))
    )
    (comp (ref "R432")
      (value "5106")
      (footprint "5106")
      (description "RES, 0, 1%, 0.5 W, 0805")
      (fields
        (field (name "MANUFACTURER") "Keystone")
        (field (name "VALUEDISPLAYED") "0")
        (field (name "PUBLISHER") "Texas Instruments")
      )
      (libsource (lib "Altium Vault - TI") (part "Resistor"))
    )
    (comp (ref "R434")
      (value "5106")
      (footprint "5106")
      (description "RES, 0, 1%, 0.5 W, 0805")
      (fields
        (field (name "MANUFACTURER") "Keystone")
        (field (name "VALUEDISPLAYED") "0")
        (field (name "PUBLISHER") "Texas Instruments")
      )
      (libsource (lib "Altium Vault - TI") (part "Resistor"))
    )
    (comp (ref "R436")
      (value "5106")
      (footprint "5106")
      (description "RES, 0, 1%, 0.5 W, 0805")
      (fields
        (field (name "MANUFACTURER") "Keystone")
        (field (name "VALUEDISPLAYED") "0")
        (field (name "PUBLISHER") "Texas Instruments")
      )
      (libsource (lib "Altium Vault - TI") (part "Resistor"))
    )
    (comp (ref "R438")
      (value "5106")
      (footprint "5106")
      (description "RES, 0, 1%, 0.5 W, 0805")
      (fields
        (field (name "MANUFACTURER") "Keystone")
        (field (name "VALUEDISPLAYED") "0")
        (field (name "PUBLISHER") "Texas Instruments")
      )
      (libsource (lib "Altium Vault - TI") (part "Resistor"))
    )
    (comp (ref "R440")
      (value "5106")
      (footprint "5106")
      (description "RES, 0, 1%, 0.5 W, 0805")
      (fields
        (field (name "MANUFACTURER") "Keystone")
        (field (name "VALUEDISPLAYED") "0")
        (field (name "PUBLISHER") "Texas Instruments")
      )
      (libsource (lib "Altium Vault - TI") (part "Resistor"))
    )
    (comp (ref "R442")
      (value "5106")
      (footprint "5106")
      (description "RES, 0, 1%, 0.5 W, 0805")
      (fields
        (field (name "MANUFACTURER") "Keystone")
        (field (name "VALUEDISPLAYED") "0")
        (field (name "PUBLISHER") "Texas Instruments")
      )
      (libsource (lib "Altium Vault - TI") (part "Resistor"))
    )
    (comp (ref "R444")
      (value "5106")
      (footprint "5106")
      (description "RES, 0, 1%, 0.5 W, 0805")
      (fields
        (field (name "MANUFACTURER") "Keystone")
        (field (name "VALUEDISPLAYED") "0")
        (field (name "PUBLISHER") "Texas Instruments")
      )
      (libsource (lib "Altium Vault - TI") (part "Resistor"))
    )
    (comp (ref "R446")
      (value "5106")
      (footprint "5106")
      (description "RES, 0, 1%, 0.5 W, 0805")
      (fields
        (field (name "MANUFACTURER") "Keystone")
        (field (name "VALUEDISPLAYED") "0")
        (field (name "PUBLISHER") "Texas Instruments")
      )
      (libsource (lib "Altium Vault - TI") (part "Resistor"))
    )
    (comp (ref "R448")
      (value "5106")
      (footprint "5106")
      (description "RES, 0, 1%, 0.5 W, 0805")
      (fields
        (field (name "MANUFACTURER") "Keystone")
        (field (name "VALUEDISPLAYED") "0")
        (field (name "PUBLISHER") "Texas Instruments")
      )
      (libsource (lib "Altium Vault - TI") (part "Resistor"))
    )
    (comp (ref "R450")
      (value "5106")
      (footprint "5106")
      (description "RES, 0, 1%, 0.5 W, 0805")
      (fields
        (field (name "MANUFACTURER") "Keystone")
        (field (name "VALUEDISPLAYED") "0")
        (field (name "PUBLISHER") "Texas Instruments")
      )
      (libsource (lib "Altium Vault - TI") (part "Resistor"))
    )
    (comp (ref "R452")
      (value "5106")
      (footprint "5106")
      (description "RES, 0, 1%, 0.5 W, 0805")
      (fields
        (field (name "MANUFACTURER") "Keystone")
        (field (name "VALUEDISPLAYED") "0")
        (field (name "PUBLISHER") "Texas Instruments")
      )
      (libsource (lib "Altium Vault - TI") (part "Resistor"))
    )
    (comp (ref "R454")
      (value "5106")
      (footprint "5106")
      (description "RES, 0, 1%, 0.5 W, 0805")
      (fields
        (field (name "MANUFACTURER") "Keystone")
        (field (name "VALUEDISPLAYED") "0")
        (field (name "PUBLISHER") "Texas Instruments")
      )
      (libsource (lib "Altium Vault - TI") (part "Resistor"))
    )
    (comp (ref "R456")
      (value "CRCW25121K00FKEG")
      (footprint "2512")
      (description "RES, 1.00 k, 1%, 1 W, AEC-Q200 Grade 0, 2512")
      (fields (field (name "MANUFACTURER") "Vishay-Dale") (field (name "VALUEDISPLAYED") "1.00k"))
      (libsource (lib "Altium Vault - TI") (part "Resistor"))
    )
    (comp (ref "R457")
      (value "CRCW25121K00FKEG")
      (footprint "2512")
      (description "RES, 1.00 k, 1%, 1 W, AEC-Q200 Grade 0, 2512")
      (fields (field (name "MANUFACTURER") "Vishay-Dale") (field (name "VALUEDISPLAYED") "1.00k"))
      (libsource (lib "Altium Vault - TI") (part "Resistor"))
    )
    (comp (ref "R458")
      (value "CRCW25121K00FKEG")
      (footprint "2512")
      (description "RES, 1.00 k, 1%, 1 W, AEC-Q200 Grade 0, 2512")
      (fields (field (name "MANUFACTURER") "Vishay-Dale") (field (name "VALUEDISPLAYED") "1.00k"))
      (libsource (lib "Altium Vault - TI") (part "Resistor"))
    )
    (comp (ref "R459")
      (value "CRCW25121K00FKEG")
      (footprint "2512")
      (description "RES, 1.00 k, 1%, 1 W, AEC-Q200 Grade 0, 2512")
      (fields (field (name "MANUFACTURER") "Vishay-Dale") (field (name "VALUEDISPLAYED") "1.00k"))
      (libsource (lib "Altium Vault - TI") (part "Resistor"))
    )
    (comp (ref "R460")
      (value "CRCW25121K00FKEG")
      (footprint "2512")
      (description "RES, 1.00 k, 1%, 1 W, AEC-Q200 Grade 0, 2512")
      (fields (field (name "MANUFACTURER") "Vishay-Dale") (field (name "VALUEDISPLAYED") "1.00k"))
      (libsource (lib "Altium Vault - TI") (part "Resistor"))
    )
    (comp (ref "R461")
      (value "CRCW25121K00FKEG")
      (footprint "2512")
      (description "RES, 1.00 k, 1%, 1 W, AEC-Q200 Grade 0, 2512")
      (fields (field (name "MANUFACTURER") "Vishay-Dale") (field (name "VALUEDISPLAYED") "1.00k"))
      (libsource (lib "Altium Vault - TI") (part "Resistor"))
    )
    (comp (ref "R468")
      (value "5106")
      (footprint "5106")
      (description "RES, 0, 1%, 0.5 W, 0805")
      (fields
        (field (name "MANUFACTURER") "Keystone")
        (field (name "VALUEDISPLAYED") "0")
        (field (name "PUBLISHER") "Texas Instruments")
      )
      (libsource (lib "Altium Vault - TI") (part "Resistor"))
    )
    (comp (ref "R470")
      (value "5106")
      (footprint "5106")
      (description "RES, 0, 1%, 0.5 W, 0805")
      (fields
        (field (name "MANUFACTURER") "Keystone")
        (field (name "VALUEDISPLAYED") "0")
        (field (name "PUBLISHER") "Texas Instruments")
      )
      (libsource (lib "Altium Vault - TI") (part "Resistor"))
    )
    (comp (ref "R472")
      (value "5106")
      (footprint "5106")
      (description "RES, 0, 1%, 0.5 W, 0805")
      (fields
        (field (name "MANUFACTURER") "Keystone")
        (field (name "VALUEDISPLAYED") "0")
        (field (name "PUBLISHER") "Texas Instruments")
      )
      (libsource (lib "Altium Vault - TI") (part "Resistor"))
    )
    (comp (ref "R474")
      (value "5106")
      (footprint "5106")
      (description "RES, 0, 1%, 0.5 W, 0805")
      (fields
        (field (name "MANUFACTURER") "Keystone")
        (field (name "VALUEDISPLAYED") "0")
        (field (name "PUBLISHER") "Texas Instruments")
      )
      (libsource (lib "Altium Vault - TI") (part "Resistor"))
    )
    (comp (ref "R476")
      (value "5106")
      (footprint "5106")
      (description "RES, 0, 1%, 0.5 W, 0805")
      (fields
        (field (name "MANUFACTURER") "Keystone")
        (field (name "VALUEDISPLAYED") "0")
        (field (name "PUBLISHER") "Texas Instruments")
      )
      (libsource (lib "Altium Vault - TI") (part "Resistor"))
    )
    (comp (ref "R478")
      (value "5106")
      (footprint "5106")
      (description "RES, 0, 1%, 0.5 W, 0805")
      (fields
        (field (name "MANUFACTURER") "Keystone")
        (field (name "VALUEDISPLAYED") "0")
        (field (name "PUBLISHER") "Texas Instruments")
      )
      (libsource (lib "Altium Vault - TI") (part "Resistor"))
    )
    (comp (ref "R480")
      (value "5106")
      (footprint "5106")
      (description "RES, 0, 1%, 0.5 W, 0805")
      (fields
        (field (name "MANUFACTURER") "Keystone")
        (field (name "VALUEDISPLAYED") "0")
        (field (name "PUBLISHER") "Texas Instruments")
      )
      (libsource (lib "Altium Vault - TI") (part "Resistor"))
    )
    (comp (ref "R482")
      (value "5106")
      (footprint "5106")
      (description "RES, 0, 1%, 0.5 W, 0805")
      (fields
        (field (name "MANUFACTURER") "Keystone")
        (field (name "VALUEDISPLAYED") "0")
        (field (name "PUBLISHER") "Texas Instruments")
      )
      (libsource (lib "Altium Vault - TI") (part "Resistor"))
    )
    (comp (ref "R484")
      (value "5106")
      (footprint "5106")
      (description "RES, 0, 1%, 0.5 W, 0805")
      (fields
        (field (name "MANUFACTURER") "Keystone")
        (field (name "VALUEDISPLAYED") "0")
        (field (name "PUBLISHER") "Texas Instruments")
      )
      (libsource (lib "Altium Vault - TI") (part "Resistor"))
    )
    (comp (ref "R486")
      (value "5106")
      (footprint "5106")
      (description "RES, 0, 1%, 0.5 W, 0805")
      (fields
        (field (name "MANUFACTURER") "Keystone")
        (field (name "VALUEDISPLAYED") "0")
        (field (name "PUBLISHER") "Texas Instruments")
      )
      (libsource (lib "Altium Vault - TI") (part "Resistor"))
    )
    (comp (ref "R488")
      (value "5106")
      (footprint "5106")
      (description "RES, 0, 1%, 0.5 W, 0805")
      (fields
        (field (name "MANUFACTURER") "Keystone")
        (field (name "VALUEDISPLAYED") "0")
        (field (name "PUBLISHER") "Texas Instruments")
      )
      (libsource (lib "Altium Vault - TI") (part "Resistor"))
    )
    (comp (ref "R490")
      (value "5106")
      (footprint "5106")
      (description "RES, 0, 1%, 0.5 W, 0805")
      (fields
        (field (name "MANUFACTURER") "Keystone")
        (field (name "VALUEDISPLAYED") "0")
        (field (name "PUBLISHER") "Texas Instruments")
      )
      (libsource (lib "Altium Vault - TI") (part "Resistor"))
    )
    (comp (ref "R492")
      (value "CRCW25121K00FKEG")
      (footprint "2512")
      (description "RES, 1.00 k, 1%, 1 W, AEC-Q200 Grade 0, 2512")
      (fields (field (name "MANUFACTURER") "Vishay-Dale") (field (name "VALUEDISPLAYED") "1.00k"))
      (libsource (lib "Altium Vault - TI") (part "Resistor"))
    )
    (comp (ref "R493")
      (value "CRCW25121K00FKEG")
      (footprint "2512")
      (description "RES, 1.00 k, 1%, 1 W, AEC-Q200 Grade 0, 2512")
      (fields (field (name "MANUFACTURER") "Vishay-Dale") (field (name "VALUEDISPLAYED") "1.00k"))
      (libsource (lib "Altium Vault - TI") (part "Resistor"))
    )
    (comp (ref "R494")
      (value "CRCW25121K00FKEG")
      (footprint "2512")
      (description "RES, 1.00 k, 1%, 1 W, AEC-Q200 Grade 0, 2512")
      (fields (field (name "MANUFACTURER") "Vishay-Dale") (field (name "VALUEDISPLAYED") "1.00k"))
      (libsource (lib "Altium Vault - TI") (part "Resistor"))
    )
    (comp (ref "R495")
      (value "CRCW25121K00FKEG")
      (footprint "2512")
      (description "RES, 1.00 k, 1%, 1 W, AEC-Q200 Grade 0, 2512")
      (fields (field (name "MANUFACTURER") "Vishay-Dale") (field (name "VALUEDISPLAYED") "1.00k"))
      (libsource (lib "Altium Vault - TI") (part "Resistor"))
    )
    (comp (ref "R496")
      (value "CRCW25121K00FKEG")
      (footprint "2512")
      (description "RES, 1.00 k, 1%, 1 W, AEC-Q200 Grade 0, 2512")
      (fields (field (name "MANUFACTURER") "Vishay-Dale") (field (name "VALUEDISPLAYED") "1.00k"))
      (libsource (lib "Altium Vault - TI") (part "Resistor"))
    )
    (comp (ref "R497")
      (value "CRCW25121K00FKEG")
      (footprint "2512")
      (description "RES, 1.00 k, 1%, 1 W, AEC-Q200 Grade 0, 2512")
      (fields (field (name "MANUFACTURER") "Vishay-Dale") (field (name "VALUEDISPLAYED") "1.00k"))
      (libsource (lib "Altium Vault - TI") (part "Resistor"))
    )
    (comp (ref "R504")
      (value "5106")
      (footprint "5106")
      (description "RES, 0, 1%, 0.5 W, 0805")
      (fields
        (field (name "MANUFACTURER") "Keystone")
        (field (name "VALUEDISPLAYED") "0")
        (field (name "PUBLISHER") "Texas Instruments")
      )
      (libsource (lib "Altium Vault - TI") (part "Resistor"))
    )
    (comp (ref "R506")
      (value "5106")
      (footprint "5106")
      (description "RES, 0, 1%, 0.5 W, 0805")
      (fields
        (field (name "MANUFACTURER") "Keystone")
        (field (name "VALUEDISPLAYED") "0")
        (field (name "PUBLISHER") "Texas Instruments")
      )
      (libsource (lib "Altium Vault - TI") (part "Resistor"))
    )
    (comp (ref "R508")
      (value "5106")
      (footprint "5106")
      (description "RES, 0, 1%, 0.5 W, 0805")
      (fields
        (field (name "MANUFACTURER") "Keystone")
        (field (name "VALUEDISPLAYED") "0")
        (field (name "PUBLISHER") "Texas Instruments")
      )
      (libsource (lib "Altium Vault - TI") (part "Resistor"))
    )
    (comp (ref "R510")
      (value "5106")
      (footprint "5106")
      (description "RES, 0, 1%, 0.5 W, 0805")
      (fields
        (field (name "MANUFACTURER") "Keystone")
        (field (name "VALUEDISPLAYED") "0")
        (field (name "PUBLISHER") "Texas Instruments")
      )
      (libsource (lib "Altium Vault - TI") (part "Resistor"))
    )
    (comp (ref "R512")
      (value "5106")
      (footprint "5106")
      (description "RES, 0, 1%, 0.5 W, 0805")
      (fields
        (field (name "MANUFACTURER") "Keystone")
        (field (name "VALUEDISPLAYED") "0")
        (field (name "PUBLISHER") "Texas Instruments")
      )
      (libsource (lib "Altium Vault - TI") (part "Resistor"))
    )
    (comp (ref "R514")
      (value "5106")
      (footprint "5106")
      (description "RES, 0, 1%, 0.5 W, 0805")
      (fields
        (field (name "MANUFACTURER") "Keystone")
        (field (name "VALUEDISPLAYED") "0")
        (field (name "PUBLISHER") "Texas Instruments")
      )
      (libsource (lib "Altium Vault - TI") (part "Resistor"))
    )
    (comp (ref "R516")
      (value "5106")
      (footprint "5106")
      (description "RES, 0, 1%, 0.5 W, 0805")
      (fields
        (field (name "MANUFACTURER") "Keystone")
        (field (name "VALUEDISPLAYED") "0")
        (field (name "PUBLISHER") "Texas Instruments")
      )
      (libsource (lib "Altium Vault - TI") (part "Resistor"))
    )
    (comp (ref "R518")
      (value "5106")
      (footprint "5106")
      (description "RES, 0, 1%, 0.5 W, 0805")
      (fields
        (field (name "MANUFACTURER") "Keystone")
        (field (name "VALUEDISPLAYED") "0")
        (field (name "PUBLISHER") "Texas Instruments")
      )
      (libsource (lib "Altium Vault - TI") (part "Resistor"))
    )
    (comp (ref "R520")
      (value "5106")
      (footprint "5106")
      (description "RES, 0, 1%, 0.5 W, 0805")
      (fields
        (field (name "MANUFACTURER") "Keystone")
        (field (name "VALUEDISPLAYED") "0")
        (field (name "PUBLISHER") "Texas Instruments")
      )
      (libsource (lib "Altium Vault - TI") (part "Resistor"))
    )
    (comp (ref "R522")
      (value "5106")
      (footprint "5106")
      (description "RES, 0, 1%, 0.5 W, 0805")
      (fields
        (field (name "MANUFACTURER") "Keystone")
        (field (name "VALUEDISPLAYED") "0")
        (field (name "PUBLISHER") "Texas Instruments")
      )
      (libsource (lib "Altium Vault - TI") (part "Resistor"))
    )
    (comp (ref "R524")
      (value "5106")
      (footprint "5106")
      (description "RES, 0, 1%, 0.5 W, 0805")
      (fields
        (field (name "MANUFACTURER") "Keystone")
        (field (name "VALUEDISPLAYED") "0")
        (field (name "PUBLISHER") "Texas Instruments")
      )
      (libsource (lib "Altium Vault - TI") (part "Resistor"))
    )
    (comp (ref "R526")
      (value "5106")
      (footprint "5106")
      (description "RES, 0, 1%, 0.5 W, 0805")
      (fields
        (field (name "MANUFACTURER") "Keystone")
        (field (name "VALUEDISPLAYED") "0")
        (field (name "PUBLISHER") "Texas Instruments")
      )
      (libsource (lib "Altium Vault - TI") (part "Resistor"))
    )
    (comp (ref "R528")
      (value "CRCW25121K00FKEG")
      (footprint "2512")
      (description "RES, 1.00 k, 1%, 1 W, AEC-Q200 Grade 0, 2512")
      (fields (field (name "MANUFACTURER") "Vishay-Dale") (field (name "VALUEDISPLAYED") "1.00k"))
      (libsource (lib "Altium Vault - TI") (part "Resistor"))
    )
    (comp (ref "R529")
      (value "CRCW25121K00FKEG")
      (footprint "2512")
      (description "RES, 1.00 k, 1%, 1 W, AEC-Q200 Grade 0, 2512")
      (fields (field (name "MANUFACTURER") "Vishay-Dale") (field (name "VALUEDISPLAYED") "1.00k"))
      (libsource (lib "Altium Vault - TI") (part "Resistor"))
    )
    (comp (ref "R530")
      (value "CRCW25121K00FKEG")
      (footprint "2512")
      (description "RES, 1.00 k, 1%, 1 W, AEC-Q200 Grade 0, 2512")
      (fields (field (name "MANUFACTURER") "Vishay-Dale") (field (name "VALUEDISPLAYED") "1.00k"))
      (libsource (lib "Altium Vault - TI") (part "Resistor"))
    )
    (comp (ref "R531")
      (value "CRCW25121K00FKEG")
      (footprint "2512")
      (description "RES, 1.00 k, 1%, 1 W, AEC-Q200 Grade 0, 2512")
      (fields (field (name "MANUFACTURER") "Vishay-Dale") (field (name "VALUEDISPLAYED") "1.00k"))
      (libsource (lib "Altium Vault - TI") (part "Resistor"))
    )
    (comp (ref "R532")
      (value "CRCW25121K00FKEG")
      (footprint "2512")
      (description "RES, 1.00 k, 1%, 1 W, AEC-Q200 Grade 0, 2512")
      (fields (field (name "MANUFACTURER") "Vishay-Dale") (field (name "VALUEDISPLAYED") "1.00k"))
      (libsource (lib "Altium Vault - TI") (part "Resistor"))
    )
    (comp (ref "R533")
      (value "CRCW25121K00FKEG")
      (footprint "2512")
      (description "RES, 1.00 k, 1%, 1 W, AEC-Q200 Grade 0, 2512")
      (fields (field (name "MANUFACTURER") "Vishay-Dale") (field (name "VALUEDISPLAYED") "1.00k"))
      (libsource (lib "Altium Vault - TI") (part "Resistor"))
    )
    (comp (ref "R540")
      (value "5106")
      (footprint "5106")
      (description "RES, 0, 1%, 0.5 W, 0805")
      (fields
        (field (name "MANUFACTURER") "Keystone")
        (field (name "VALUEDISPLAYED") "0")
        (field (name "PUBLISHER") "Texas Instruments")
      )
      (libsource (lib "Altium Vault - TI") (part "Resistor"))
    )
    (comp (ref "R542")
      (value "5106")
      (footprint "5106")
      (description "RES, 0, 1%, 0.5 W, 0805")
      (fields
        (field (name "MANUFACTURER") "Keystone")
        (field (name "VALUEDISPLAYED") "0")
        (field (name "PUBLISHER") "Texas Instruments")
      )
      (libsource (lib "Altium Vault - TI") (part "Resistor"))
    )
    (comp (ref "R544")
      (value "5106")
      (footprint "5106")
      (description "RES, 0, 1%, 0.5 W, 0805")
      (fields
        (field (name "MANUFACTURER") "Keystone")
        (field (name "VALUEDISPLAYED") "0")
        (field (name "PUBLISHER") "Texas Instruments")
      )
      (libsource (lib "Altium Vault - TI") (part "Resistor"))
    )
    (comp (ref "R546")
      (value "5106")
      (footprint "5106")
      (description "RES, 0, 1%, 0.5 W, 0805")
      (fields
        (field (name "MANUFACTURER") "Keystone")
        (field (name "VALUEDISPLAYED") "0")
        (field (name "PUBLISHER") "Texas Instruments")
      )
      (libsource (lib "Altium Vault - TI") (part "Resistor"))
    )
    (comp (ref "R548")
      (value "5106")
      (footprint "5106")
      (description "RES, 0, 1%, 0.5 W, 0805")
      (fields
        (field (name "MANUFACTURER") "Keystone")
        (field (name "VALUEDISPLAYED") "0")
        (field (name "PUBLISHER") "Texas Instruments")
      )
      (libsource (lib "Altium Vault - TI") (part "Resistor"))
    )
    (comp (ref "R550")
      (value "5106")
      (footprint "5106")
      (description "RES, 0, 1%, 0.5 W, 0805")
      (fields
        (field (name "MANUFACTURER") "Keystone")
        (field (name "VALUEDISPLAYED") "0")
        (field (name "PUBLISHER") "Texas Instruments")
      )
      (libsource (lib "Altium Vault - TI") (part "Resistor"))
    )
    (comp (ref "R552")
      (value "5106")
      (footprint "5106")
      (description "RES, 0, 1%, 0.5 W, 0805")
      (fields
        (field (name "MANUFACTURER") "Keystone")
        (field (name "VALUEDISPLAYED") "0")
        (field (name "PUBLISHER") "Texas Instruments")
      )
      (libsource (lib "Altium Vault - TI") (part "Resistor"))
    )
    (comp (ref "R554")
      (value "5106")
      (footprint "5106")
      (description "RES, 0, 1%, 0.5 W, 0805")
      (fields
        (field (name "MANUFACTURER") "Keystone")
        (field (name "VALUEDISPLAYED") "0")
        (field (name "PUBLISHER") "Texas Instruments")
      )
      (libsource (lib "Altium Vault - TI") (part "Resistor"))
    )
    (comp (ref "R556")
      (value "CRCW25121K00FKEG")
      (footprint "2512")
      (description "RES, 1.00 k, 1%, 1 W, AEC-Q200 Grade 0, 2512")
      (fields (field (name "MANUFACTURER") "Vishay-Dale") (field (name "VALUEDISPLAYED") "1.00k"))
      (libsource (lib "Altium Vault - TI") (part "Resistor"))
    )
    (comp (ref "R557")
      (value "CRCW25121K00FKEG")
      (footprint "2512")
      (description "RES, 1.00 k, 1%, 1 W, AEC-Q200 Grade 0, 2512")
      (fields (field (name "MANUFACTURER") "Vishay-Dale") (field (name "VALUEDISPLAYED") "1.00k"))
      (libsource (lib "Altium Vault - TI") (part "Resistor"))
    )
    (comp (ref "R560")
      (value "5106")
      (footprint "5106")
      (description "RES, 0, 1%, 0.5 W, 0805")
      (fields
        (field (name "MANUFACTURER") "Keystone")
        (field (name "VALUEDISPLAYED") "0")
        (field (name "PUBLISHER") "Texas Instruments")
      )
      (libsource (lib "Altium Vault - TI") (part "Resistor"))
    )
    (comp (ref "R562")
      (value "5106")
      (footprint "5106")
      (description "RES, 0, 1%, 0.5 W, 0805")
      (fields
        (field (name "MANUFACTURER") "Keystone")
        (field (name "VALUEDISPLAYED") "0")
        (field (name "PUBLISHER") "Texas Instruments")
      )
      (libsource (lib "Altium Vault - TI") (part "Resistor"))
    )
    (comp (ref "R564")
      (value "Resistor")
      (footprint "1206")
      (description "RES, 1.02 k, 1%, 0.25 W, AEC-Q200 Grade 0, 1206")
      (fields
        (field (name "PARTNUMBER") "CRCW12061K02FKEA")
        (field (name "VALUEDISPLAYED") "1.02k")
        (field (name "MANUFACTURER") "Vishay-Dale")
      )
      (libsource (lib "Altium Vault - TI") (part "CMP-0016688-3"))
    )
    (comp (ref "R565")
      (value "TNPW060349R9BEEA")
      (footprint "TNPW0603")
      (description "RES, 49.9, 0.1%, 0.1 W, AEC-Q200 Grade 1, 0603")
      (fields
        (field (name "MANUFACTURER") "Vishay-Dale")
        (field (name "VALUEDISPLAYED") "49.9")
        (field (name "PUBLISHER") "Texas Instruments")
      )
      (libsource (lib "Altium Vault - TI") (part "Resistor"))
    )
    (comp (ref "TP48")
      (value "TESTPOINT")
      (footprint "TP_50MIL-SMT")
      (description "TEST POINT.  No entry in BOM.")
      (libsource (lib "Altium Vault - TI") (part "TESTPOINT"))
    )
    (comp (ref "TP49")
      (value "TESTPOINT")
      (footprint "TP_50MIL-SMT")
      (description "TEST POINT.  No entry in BOM.")
      (libsource (lib "Altium Vault - TI") (part "TESTPOINT"))
    )
    (comp (ref "TP53")
      (value "TESTPOINT")
      (footprint "TP_50MIL-SMT")
      (description "TEST POINT.  No entry in BOM.")
      (libsource (lib "Altium Vault - TI") (part "TESTPOINT"))
    )
    (comp (ref "TP55")
      (value "TESTPOINT")
      (footprint "TP_50MIL-SMT")
      (description "TEST POINT.  No entry in BOM.")
      (libsource (lib "Altium Vault - TI") (part "TESTPOINT"))
    )
    (comp (ref "TP56")
      (value "TESTPOINT")
      (footprint "TP_50MIL-SMT")
      (description "TEST POINT.  No entry in BOM.")
      (libsource (lib "Altium Vault - TI") (part "TESTPOINT"))
    )
    (comp (ref "TP57")
      (value "TESTPOINT")
      (footprint "TP_50MIL-SMT")
      (description "TEST POINT.  No entry in BOM.")
      (libsource (lib "Altium Vault - TI") (part "TESTPOINT"))
    )
    (comp (ref "TP58")
      (value "TESTPOINT")
      (footprint "TP_50MIL-SMT")
      (description "TEST POINT.  No entry in BOM.")
      (libsource (lib "Altium Vault - TI") (part "TESTPOINT"))
    )
    (comp (ref "TP60")
      (value "TESTPOINT")
      (footprint "TP_50MIL-SMT")
      (description "TEST POINT.  No entry in BOM.")
      (libsource (lib "Altium Vault - TI") (part "TESTPOINT"))
    )
    (comp (ref "TP61")
      (value "TESTPOINT")
      (footprint "TP_50MIL-SMT")
      (description "TEST POINT.  No entry in BOM.")
      (libsource (lib "Altium Vault - TI") (part "TESTPOINT"))
    )
    (comp (ref "TP62")
      (value "TESTPOINT")
      (footprint "TP_50MIL-SMT")
      (description "TEST POINT.  No entry in BOM.")
      (libsource (lib "Altium Vault - TI") (part "TESTPOINT"))
    )
    (comp (ref "TP63")
      (value "TESTPOINT")
      (footprint "TP_50MIL-SMT")
      (description "TEST POINT.  No entry in BOM.")
      (libsource (lib "Altium Vault - TI") (part "TESTPOINT"))
    )
    (comp (ref "TP64")
      (value "TESTPOINT")
      (footprint "TP_50MIL-SMT")
      (description "TEST POINT.  No entry in BOM.")
      (libsource (lib "Altium Vault - TI") (part "TESTPOINT"))
    )
    (comp (ref "TP65")
      (value "TESTPOINT")
      (footprint "TP_50MIL-SMT")
      (description "TEST POINT.  No entry in BOM.")
      (libsource (lib "Altium Vault - TI") (part "TESTPOINT"))
    )
    (comp (ref "TP66")
      (value "TESTPOINT")
      (footprint "TP_50MIL-SMT")
      (description "TEST POINT.  No entry in BOM.")
      (libsource (lib "Altium Vault - TI") (part "TESTPOINT"))
    )
    (comp (ref "TP67")
      (value "TESTPOINT")
      (footprint "TP_50MIL-SMT")
      (description "TEST POINT.  No entry in BOM.")
      (libsource (lib "Altium Vault - TI") (part "TESTPOINT"))
    )
    (comp (ref "TP68")
      (value "TESTPOINT")
      (footprint "TP_50MIL-SMT")
      (description "TEST POINT.  No entry in BOM.")
      (libsource (lib "Altium Vault - TI") (part "TESTPOINT"))
    )
    (comp (ref "TP85")
      (value "TESTPOINT")
      (footprint "TP_50MIL-SMT")
      (description "TEST POINT.  No entry in BOM.")
      (libsource (lib "Altium Vault - TI") (part "TESTPOINT"))
    )
    (comp (ref "TP86")
      (value "TESTPOINT")
      (footprint "TP_50MIL-SMT")
      (description "TEST POINT.  No entry in BOM.")
      (libsource (lib "Altium Vault - TI") (part "TESTPOINT"))
    )
    (comp (ref "TP87")
      (value "TESTPOINT")
      (footprint "TP_50MIL-SMT")
      (description "TEST POINT.  No entry in BOM.")
      (libsource (lib "Altium Vault - TI") (part "TESTPOINT"))
    )
    (comp (ref "TP88")
      (value "TESTPOINT")
      (footprint "TP_50MIL-SMT")
      (description "TEST POINT.  No entry in BOM.")
      (libsource (lib "Altium Vault - TI") (part "TESTPOINT"))
    )
    (comp (ref "TP89")
      (value "TESTPOINT")
      (footprint "TP_50MIL-SMT")
      (description "TEST POINT.  No entry in BOM.")
      (libsource (lib "Altium Vault - TI") (part "TESTPOINT"))
    )
    (comp (ref "TP90")
      (value "TESTPOINT")
      (footprint "TP_50MIL-SMT")
      (description "TEST POINT.  No entry in BOM.")
      (libsource (lib "Altium Vault - TI") (part "TESTPOINT"))
    )
    (comp (ref "TP91")
      (value "TESTPOINT")
      (footprint "TP_50MIL-SMT")
      (description "TEST POINT.  No entry in BOM.")
      (libsource (lib "Altium Vault - TI") (part "TESTPOINT"))
    )
    (comp (ref "TP92")
      (value "TESTPOINT")
      (footprint "TP_50MIL-SMT")
      (description "TEST POINT.  No entry in BOM.")
      (libsource (lib "Altium Vault - TI") (part "TESTPOINT"))
    )
    (comp (ref "TP93")
      (value "TESTPOINT")
      (footprint "TP_50MIL-SMT")
      (description "TEST POINT.  No entry in BOM.")
      (libsource (lib "Altium Vault - TI") (part "TESTPOINT"))
    )
    (comp (ref "TP94")
      (value "TESTPOINT")
      (footprint "TP_50MIL-SMT")
      (description "TEST POINT.  No entry in BOM.")
      (libsource (lib "Altium Vault - TI") (part "TESTPOINT"))
    )
    (comp (ref "TP95")
      (value "TESTPOINT")
      (footprint "TP_50MIL-SMT")
      (description "TEST POINT.  No entry in BOM.")
      (libsource (lib "Altium Vault - TI") (part "TESTPOINT"))
    )
    (comp (ref "TP96")
      (value "TESTPOINT")
      (footprint "TP_50MIL-SMT")
      (description "TEST POINT.  No entry in BOM.")
      (libsource (lib "Altium Vault - TI") (part "TESTPOINT"))
    )
    (comp (ref "TP97")
      (value "TESTPOINT")
      (footprint "TP_50MIL-SMT")
      (description "TEST POINT.  No entry in BOM.")
      (libsource (lib "Altium Vault - TI") (part "TESTPOINT"))
    )
    (comp (ref "TP98")
      (value "TESTPOINT")
      (footprint "TP_50MIL-SMT")
      (description "TEST POINT.  No entry in BOM.")
      (libsource (lib "Altium Vault - TI") (part "TESTPOINT"))
    )
    (comp (ref "TP99")
      (value "TESTPOINT")
      (footprint "TP_50MIL-SMT")
      (description "TEST POINT.  No entry in BOM.")
      (libsource (lib "Altium Vault - TI") (part "TESTPOINT"))
    )
    (comp (ref "TP100")
      (value "TESTPOINT")
      (footprint "TP_50MIL-SMT")
      (description "TEST POINT.  No entry in BOM.")
      (libsource (lib "Altium Vault - TI") (part "TESTPOINT"))
    )
  )
  (nets
    (net (code "1") (name "/OUT1") (class "Default")
      (node (ref "R352") (pin "1") (pinfunction "1_1") (pintype "passive"))
    )
    (net (code "2") (name "/OUT2") (class "Default")
      (node (ref "R347") (pin "1") (pinfunction "1_1") (pintype "passive"))
    )
    (net (code "3") (name "/OUT3") (class "Default")
      (node (ref "R362") (pin "1") (pinfunction "1_1") (pintype "passive"))
      (node (ref "TP53") (pin "1") (pintype "passive"))
    )
    (net (code "4") (name "/OUT4") (class "Default")
      (node (ref "R387") (pin "1") (pinfunction "1_1") (pintype "passive"))
      (node (ref "TP55") (pin "1") (pintype "passive"))
    )
    (net (code "5") (name "/OUT5") (class "Default")
      (node (ref "R365") (pin "1") (pinfunction "1_1") (pintype "passive"))
    )
    (net (code "6") (name "/OUT6") (class "Default")
      (node (ref "R389") (pin "1") (pinfunction "1_1") (pintype "passive"))
    )
    (net (code "7") (name "/OUT7") (class "Default")
      (node (ref "R369") (pin "1") (pinfunction "1_1") (pintype "passive"))
    )
    (net (code "8") (name "/OUT8") (class "Default")
      (node (ref "R391") (pin "1") (pinfunction "1_1") (pintype "passive"))
    )
    (net (code "9") (name "/OUT9") (class "Default")
      (node (ref "R371") (pin "1") (pinfunction "1_1") (pintype "passive"))
      (node (ref "TP85") (pin "1") (pintype "passive"))
    )
    (net (code "10") (name "/OUT10") (class "Default")
      (node (ref "R393") (pin "1") (pinfunction "1_1") (pintype "passive"))
      (node (ref "TP86") (pin "1") (pintype "passive"))
    )
    (net (code "11") (name "/OUT11") (class "Default")
      (node (ref "R373") (pin "1") (pinfunction "1_1") (pintype "passive"))
    )
    (net (code "12") (name "/OUT12") (class "Default")
      (node (ref "R395") (pin "1") (pinfunction "1_1") (pintype "passive"))
    )
    (net (code "13") (name "/OUT13") (class "Default")
      (node (ref "R397") (pin "1") (pinfunction "1_1") (pintype "passive"))
    )
    (net (code "14") (name "/OUT14") (class "Default")
      (node (ref "R432") (pin "1") (pinfunction "1_1") (pintype "passive"))
    )
    (net (code "15") (name "/OUT15") (class "Default")
      (node (ref "R399") (pin "1") (pinfunction "1_1") (pintype "passive"))
      (node (ref "TP56") (pin "1") (pintype "passive"))
    )
    (net (code "16") (name "/OUT16") (class "Default")
      (node (ref "R434") (pin "1") (pinfunction "1_1") (pintype "passive"))
      (node (ref "TP60") (pin "1") (pintype "passive"))
    )
    (net (code "17") (name "/OUT17") (class "Default")
      (node (ref "R404") (pin "1") (pinfunction "1_1") (pintype "passive"))
    )
    (net (code "18") (name "/OUT18") (class "Default")
      (node (ref "R436") (pin "1") (pinfunction "1_1") (pintype "passive"))
    )
    (net (code "19") (name "/OUT19") (class "Default")
      (node (ref "R406") (pin "1") (pinfunction "1_1") (pintype "passive"))
      (node (ref "TP57") (pin "1") (pintype "passive"))
    )
    (net (code "20") (name "/OUT20") (class "Default")
      (node (ref "R438") (pin "1") (pinfunction "1_1") (pintype "passive"))
      (node (ref "TP61") (pin "1") (pintype "passive"))
    )
    (net (code "21") (name "/OUT21") (class "Default")
      (node (ref "R408") (pin "1") (pinfunction "1_1") (pintype "passive"))
      (node (ref "TP58") (pin "1") (pintype "passive"))
    )
    (net (code "22") (name "/OUT22") (class "Default")
      (node (ref "R440") (pin "1") (pinfunction "1_1") (pintype "passive"))
      (node (ref "TP62") (pin "1") (pintype "passive"))
    )
    (net (code "23") (name "/OUT23") (class "Default")
      (node (ref "R410") (pin "1") (pinfunction "1_1") (pintype "passive"))
      (node (ref "TP87") (pin "1") (pintype "passive"))
    )
    (net (code "24") (name "/OUT24") (class "Default")
      (node (ref "R442") (pin "1") (pinfunction "1_1") (pintype "passive"))
      (node (ref "TP88") (pin "1") (pintype "passive"))
    )
    (net (code "25") (name "/OUT25") (class "Default")
      (node (ref "R444") (pin "1") (pinfunction "1_1") (pintype "passive"))
      (node (ref "TP89") (pin "1") (pintype "passive"))
    )
    (net (code "26") (name "/OUT26") (class "Default")
      (node (ref "R468") (pin "1") (pinfunction "1_1") (pintype "passive"))
      (node (ref "TP91") (pin "1") (pintype "passive"))
    )
    (net (code "27") (name "/OUT27") (class "Default")
      (node (ref "R446") (pin "1") (pinfunction "1_1") (pintype "passive"))
    )
    (net (code "28") (name "/OUT28") (class "Default")
      (node (ref "R470") (pin "1") (pinfunction "1_1") (pintype "passive"))
    )
    (net (code "29") (name "/OUT29") (class "Default")
      (node (ref "R448") (pin "1") (pinfunction "1_1") (pintype "passive"))
      (node (ref "TP90") (pin "1") (pintype "passive"))
    )
    (net (code "30") (name "/OUT30") (class "Default")
      (node (ref "R472") (pin "1") (pinfunction "1_1") (pintype "passive"))
      (node (ref "TP92") (pin "1") (pintype "passive"))
    )
    (net (code "31") (name "/OUT31") (class "Default")
      (node (ref "R450") (pin "1") (pinfunction "1_1") (pintype "passive"))
    )
    (net (code "32") (name "/OUT32") (class "Default")
      (node (ref "R474") (pin "1") (pinfunction "1_1") (pintype "passive"))
    )
    (net (code "33") (name "/OUT33") (class "Default")
      (node (ref "R452") (pin "1") (pinfunction "1_1") (pintype "passive"))
      (node (ref "TP63") (pin "1") (pintype "passive"))
    )
    (net (code "34") (name "/OUT34") (class "Default")
      (node (ref "R476") (pin "1") (pinfunction "1_1") (pintype "passive"))
      (node (ref "TP64") (pin "1") (pintype "passive"))
    )
    (net (code "35") (name "/OUT35") (class "Default")
      (node (ref "R454") (pin "1") (pinfunction "1_1") (pintype "passive"))
      (node (ref "TP48") (pin "1") (pintype "passive"))
    )
    (net (code "36") (name "/OUT36") (class "Default")
      (node (ref "R478") (pin "1") (pinfunction "1_1") (pintype "passive"))
      (node (ref "TP49") (pin "1") (pintype "passive"))
    )
    (net (code "37") (name "/OUT37") (class "Default")
      (node (ref "R480") (pin "1") (pinfunction "1_1") (pintype "passive"))
    )
    (net (code "38") (name "/OUT38") (class "Default")
      (node (ref "R504") (pin "1") (pinfunction "1_1") (pintype "passive"))
    )
    (net (code "39") (name "/OUT39") (class "Default")
      (node (ref "R482") (pin "1") (pinfunction "1_1") (pintype "passive"))
    )
    (net (code "40") (name "/OUT40") (class "Default")
      (node (ref "R506") (pin "1") (pinfunction "1_1") (pintype "passive"))
    )
    (net (code "41") (name "/OUT41") (class "Default")
      (node (ref "R484") (pin "1") (pinfunction "1_1") (pintype "passive"))
    )
    (net (code "42") (name "/OUT42") (class "Default")
      (node (ref "R508") (pin "1") (pinfunction "1_1") (pintype "passive"))
    )
    (net (code "43") (name "/OUT43") (class "Default")
      (node (ref "R486") (pin "1") (pinfunction "1_1") (pintype "passive"))
      (node (ref "TP93") (pin "1") (pintype "passive"))
    )
    (net (code "44") (name "/OUT44") (class "Default")
      (node (ref "R510") (pin "1") (pinfunction "1_1") (pintype "passive"))
      (node (ref "TP94") (pin "1") (pintype "passive"))
    )
    (net (code "45") (name "/OUT45") (class "Default")
      (node (ref "R488") (pin "1") (pinfunction "1_1") (pintype "passive"))
    )
    (net (code "46") (name "/OUT46") (class "Default")
      (node (ref "R512") (pin "1") (pinfunction "1_1") (pintype "passive"))
    )
    (net (code "47") (name "/OUT47") (class "Default")
      (node (ref "R490") (pin "1") (pinfunction "1_1") (pintype "passive"))
    )
    (net (code "48") (name "/OUT48") (class "Default")
      (node (ref "R514") (pin "1") (pinfunction "1_1") (pintype "passive"))
    )
    (net (code "49") (name "/OUT49") (class "Default")
      (node (ref "R516") (pin "1") (pinfunction "1_1") (pintype "passive"))
      (node (ref "TP95") (pin "1") (pintype "passive"))
    )
    (net (code "50") (name "/OUT50") (class "Default")
      (node (ref "R540") (pin "1") (pinfunction "1_1") (pintype "passive"))
      (node (ref "TP98") (pin "1") (pintype "passive"))
    )
    (net (code "51") (name "/OUT51") (class "Default")
      (node (ref "R518") (pin "1") (pinfunction "1_1") (pintype "passive"))
    )
    (net (code "52") (name "/OUT52") (class "Default")
      (node (ref "R542") (pin "1") (pinfunction "1_1") (pintype "passive"))
    )
    (net (code "53") (name "/OUT53") (class "Default")
      (node (ref "R520") (pin "1") (pinfunction "1_1") (pintype "passive"))
      (node (ref "TP96") (pin "1") (pintype "passive"))
    )
    (net (code "54") (name "/OUT54") (class "Default")
      (node (ref "R544") (pin "1") (pinfunction "1_1") (pintype "passive"))
      (node (ref "TP99") (pin "1") (pintype "passive"))
    )
    (net (code "55") (name "/OUT55") (class "Default")
      (node (ref "R522") (pin "1") (pinfunction "1_1") (pintype "passive"))
      (node (ref "TP65") (pin "1") (pintype "passive"))
    )
    (net (code "56") (name "/OUT56") (class "Default")
      (node (ref "R546") (pin "1") (pinfunction "1_1") (pintype "passive"))
      (node (ref "TP66") (pin "1") (pintype "passive"))
    )
    (net (code "57") (name "/OUT57") (class "Default")
      (node (ref "R524") (pin "1") (pinfunction "1_1") (pintype "passive"))
      (node (ref "TP97") (pin "1") (pintype "passive"))
    )
    (net (code "58") (name "/OUT58") (class "Default")
      (node (ref "R548") (pin "1") (pinfunction "1_1") (pintype "passive"))
      (node (ref "TP100") (pin "1") (pintype "passive"))
    )
    (net (code "59") (name "/OUT59") (class "Default")
      (node (ref "R526") (pin "1") (pinfunction "1_1") (pintype "passive"))
    )
    (net (code "60") (name "/OUT60") (class "Default")
      (node (ref "R550") (pin "1") (pinfunction "1_1") (pintype "passive"))
    )
    (net (code "61") (name "/OUT61") (class "Default")
      (node (ref "R552") (pin "1") (pinfunction "1_1") (pintype "passive"))
    )
    (net (code "62") (name "/OUT62") (class "Default")
      (node (ref "R560") (pin "1") (pinfunction "1_1") (pintype "passive"))
    )
    (net (code "63") (name "/OUT63") (class "Default")
      (node (ref "R554") (pin "1") (pinfunction "1_1") (pintype "passive"))
      (node (ref "TP67") (pin "1") (pintype "passive"))
    )
    (net (code "64") (name "/OUT64") (class "Default")
      (node (ref "R562") (pin "1") (pinfunction "1_1") (pintype "passive"))
      (node (ref "TP68") (pin "1") (pintype "passive"))
    )
    (net (code "65") (name "/OUT_P1") (class "Default")
      (node (ref "C217") (pin "1") (pinfunction "1_1") (pintype "passive"))
      (node (ref "C267") (pin "1") (pinfunction "1_1") (pintype "passive"))
      (node (ref "J10") (pin "5") (pinfunction "5_5") (pintype "passive"))
      (node (ref "R352") (pin "2") (pinfunction "2_2") (pintype "passive"))
      (node (ref "R52") (pin "2") (pinfunction "2_2") (pintype "passive"))
      (node (ref "R564") (pin "2") (pinfunction "2_2") (pintype "passive"))
    )
    (net (code "66") (name "/OUT_P2") (class "Default")
      (node (ref "C225") (pin "1") (pinfunction "1_1") (pintype "passive"))
      (node (ref "J10") (pin "3") (pinfunction "3_3") (pintype "passive"))
      (node (ref "R347") (pin "2") (pinfunction "2_2") (pintype "passive"))
    )
    (net (code "67") (name "/OUT_P3") (class "Default")
      (node (ref "C24") (pin "1") (pinfunction "1_1") (pintype "passive"))
      (node (ref "J10") (pin "6") (pinfunction "6_6") (pintype "passive"))
      (node (ref "R362") (pin "2") (pinfunction "2_2") (pintype "passive"))
      (node (ref "R375") (pin "2") (pinfunction "2_2") (pintype "passive"))
    )
    (net (code "68") (name "/OUT_P4") (class "Default")
      (node (ref "C155") (pin "1") (pinfunction "1_1") (pintype "passive"))
      (node (ref "J10") (pin "4") (pinfunction "4_4") (pintype "passive"))
      (node (ref "R387") (pin "2") (pinfunction "2_2") (pintype "passive"))
    )
    (net (code "69") (name "/OUT_P5") (class "Default")
      (node (ref "C70") (pin "1") (pinfunction "1_1") (pintype "passive"))
      (node (ref "J1") (pin "17") (pinfunction "17_17") (pintype "passive"))
      (node (ref "R365") (pin "2") (pinfunction "2_2") (pintype "passive"))
      (node (ref "R376") (pin "2") (pinfunction "2_2") (pintype "passive"))
    )
    (net (code "70") (name "/OUT_P6") (class "Default")
      (node (ref "C157") (pin "1") (pinfunction "1_1") (pintype "passive"))
      (node (ref "J1") (pin "15") (pinfunction "15_15") (pintype "passive"))
      (node (ref "R389") (pin "2") (pinfunction "2_2") (pintype "passive"))
    )
    (net (code "71") (name "/OUT_P7") (class "Default")
      (node (ref "C85") (pin "1") (pinfunction "1_1") (pintype "passive"))
      (node (ref "J10") (pin "11") (pinfunction "11_11") (pintype "passive"))
      (node (ref "R369") (pin "2") (pinfunction "2_2") (pintype "passive"))
      (node (ref "R377") (pin "2") (pinfunction "2_2") (pintype "passive"))
    )
    (net (code "72") (name "/OUT_P8") (class "Default")
      (node (ref "C176") (pin "1") (pinfunction "1_1") (pintype "passive"))
      (node (ref "J10") (pin "9") (pinfunction "9_9") (pintype "passive"))
      (node (ref "R391") (pin "2") (pinfunction "2_2") (pintype "passive"))
    )
    (net (code "73") (name "/OUT_P9") (class "Default")
      (node (ref "C151") (pin "1") (pinfunction "1_1") (pintype "passive"))
      (node (ref "J1") (pin "18") (pinfunction "18_18") (pintype "passive"))
      (node (ref "R371") (pin "2") (pinfunction "2_2") (pintype "passive"))
      (node (ref "R378") (pin "2") (pinfunction "2_2") (pintype "passive"))
    )
    (net (code "74") (name "/OUT_P10") (class "Default")
      (node (ref "C192") (pin "1") (pinfunction "1_1") (pintype "passive"))
      (node (ref "J1") (pin "16") (pinfunction "16_16") (pintype "passive"))
      (node (ref "R393") (pin "2") (pinfunction "2_2") (pintype "passive"))
    )
    (net (code "75") (name "/OUT_P11") (class "Default")
      (node (ref "C153") (pin "1") (pinfunction "1_1") (pintype "passive"))
      (node (ref "J10") (pin "17") (pinfunction "17_17") (pintype "passive"))
      (node (ref "R373") (pin "2") (pinfunction "2_2") (pintype "passive"))
      (node (ref "R379") (pin "2") (pinfunction "2_2") (pintype "passive"))
    )
    (net (code "76") (name "/OUT_P12") (class "Default")
      (node (ref "C206") (pin "1") (pinfunction "1_1") (pintype "passive"))
      (node (ref "J10") (pin "15") (pinfunction "15_15") (pintype "passive"))
      (node (ref "R395") (pin "2") (pinfunction "2_2") (pintype "passive"))
    )
    (net (code "77") (name "/OUT_P13") (class "Default")
      (node (ref "C208") (pin "1") (pinfunction "1_1") (pintype "passive"))
      (node (ref "J1") (pin "5") (pinfunction "5_5") (pintype "passive"))
      (node (ref "R397") (pin "2") (pinfunction "2_2") (pintype "passive"))
      (node (ref "R412") (pin "2") (pinfunction "2_2") (pintype "passive"))
    )
    (net (code "78") (name "/OUT_P14") (class "Default")
      (node (ref "C219") (pin "1") (pinfunction "1_1") (pintype "passive"))
      (node (ref "J1") (pin "3") (pinfunction "3_3") (pintype "passive"))
      (node (ref "R432") (pin "2") (pinfunction "2_2") (pintype "passive"))
    )
    (net (code "79") (name "/OUT_P15") (class "Default")
      (node (ref "C209") (pin "1") (pinfunction "1_1") (pintype "passive"))
      (node (ref "J10") (pin "18") (pinfunction "18_18") (pintype "passive"))
      (node (ref "R399") (pin "2") (pinfunction "2_2") (pintype "passive"))
      (node (ref "R413") (pin "2") (pinfunction "2_2") (pintype "passive"))
    )
    (net (code "80") (name "/OUT_P16") (class "Default")
      (node (ref "C220") (pin "1") (pinfunction "1_1") (pintype "passive"))
      (node (ref "J10") (pin "16") (pinfunction "16_16") (pintype "passive"))
      (node (ref "R434") (pin "2") (pinfunction "2_2") (pintype "passive"))
    )
    (net (code "81") (name "/OUT_P17") (class "Default")
      (node (ref "C210") (pin "1") (pinfunction "1_1") (pintype "passive"))
      (node (ref "J10") (pin "23") (pinfunction "23_23") (pintype "passive"))
      (node (ref "R404") (pin "2") (pinfunction "2_2") (pintype "passive"))
      (node (ref "R414") (pin "2") (pinfunction "2_2") (pintype "passive"))
    )
    (net (code "82") (name "/OUT_P18") (class "Default")
      (node (ref "C221") (pin "1") (pinfunction "1_1") (pintype "passive"))
      (node (ref "J10") (pin "21") (pinfunction "21_21") (pintype "passive"))
      (node (ref "R436") (pin "2") (pinfunction "2_2") (pintype "passive"))
    )
    (net (code "83") (name "/OUT_P19") (class "Default")
      (node (ref "C214") (pin "1") (pinfunction "1_1") (pintype "passive"))
      (node (ref "J10") (pin "12") (pinfunction "12_12") (pintype "passive"))
      (node (ref "R406") (pin "2") (pinfunction "2_2") (pintype "passive"))
      (node (ref "R415") (pin "2") (pinfunction "2_2") (pintype "passive"))
    )
    (net (code "84") (name "/OUT_P20") (class "Default")
      (node (ref "C222") (pin "1") (pinfunction "1_1") (pintype "passive"))
      (node (ref "J10") (pin "10") (pinfunction "10_10") (pintype "passive"))
      (node (ref "R438") (pin "2") (pinfunction "2_2") (pintype "passive"))
    )
    (net (code "85") (name "/OUT_P21") (class "Default")
      (node (ref "C216") (pin "1") (pinfunction "1_1") (pintype "passive"))
      (node (ref "J10") (pin "24") (pinfunction "24_24") (pintype "passive"))
      (node (ref "R408") (pin "2") (pinfunction "2_2") (pintype "passive"))
      (node (ref "R416") (pin "2") (pinfunction "2_2") (pintype "passive"))
    )
    (net (code "86") (name "/OUT_P22") (class "Default")
      (node (ref "C223") (pin "1") (pinfunction "1_1") (pintype "passive"))
      (node (ref "J10") (pin "22") (pinfunction "22_22") (pintype "passive"))
      (node (ref "R440") (pin "2") (pinfunction "2_2") (pintype "passive"))
    )
    (net (code "87") (name "/OUT_P23") (class "Default")
      (node (ref "C218") (pin "1") (pinfunction "1_1") (pintype "passive"))
      (node (ref "J1") (pin "24") (pinfunction "24_24") (pintype "passive"))
      (node (ref "R410") (pin "2") (pinfunction "2_2") (pintype "passive"))
      (node (ref "R417") (pin "2") (pinfunction "2_2") (pintype "passive"))
    )
    (net (code "88") (name "/OUT_P24") (class "Default")
      (node (ref "C224") (pin "1") (pinfunction "1_1") (pintype "passive"))
      (node (ref "J1") (pin "22") (pinfunction "22_22") (pintype "passive"))
      (node (ref "R442") (pin "2") (pinfunction "2_2") (pintype "passive"))
    )
    (net (code "89") (name "/OUT_P25") (class "Default")
      (node (ref "C226") (pin "1") (pinfunction "1_1") (pintype "passive"))
      (node (ref "J1") (pin "6") (pinfunction "6_6") (pintype "passive"))
      (node (ref "R444") (pin "2") (pinfunction "2_2") (pintype "passive"))
      (node (ref "R456") (pin "2") (pinfunction "2_2") (pintype "passive"))
    )
    (net (code "90") (name "/OUT_P26") (class "Default")
      (node (ref "C232") (pin "1") (pinfunction "1_1") (pintype "passive"))
      (node (ref "J1") (pin "4") (pinfunction "4_4") (pintype "passive"))
      (node (ref "R468") (pin "2") (pinfunction "2_2") (pintype "passive"))
    )
    (net (code "91") (name "/OUT_P27") (class "Default")
      (node (ref "C227") (pin "1") (pinfunction "1_1") (pintype "passive"))
      (node (ref "J1") (pin "23") (pinfunction "23_23") (pintype "passive"))
      (node (ref "R446") (pin "2") (pinfunction "2_2") (pintype "passive"))
      (node (ref "R457") (pin "2") (pinfunction "2_2") (pintype "passive"))
    )
    (net (code "92") (name "/OUT_P28") (class "Default")
      (node (ref "C233") (pin "1") (pinfunction "1_1") (pintype "passive"))
      (node (ref "J1") (pin "21") (pinfunction "21_21") (pintype "passive"))
      (node (ref "R470") (pin "2") (pinfunction "2_2") (pintype "passive"))
    )
    (net (code "93") (name "/OUT_P29") (class "Default")
      (node (ref "C228") (pin "1") (pinfunction "1_1") (pintype "passive"))
      (node (ref "J1") (pin "12") (pinfunction "12_12") (pintype "passive"))
      (node (ref "R448") (pin "2") (pinfunction "2_2") (pintype "passive"))
      (node (ref "R458") (pin "2") (pinfunction "2_2") (pintype "passive"))
    )
    (net (code "94") (name "/OUT_P30") (class "Default")
      (node (ref "C234") (pin "1") (pinfunction "1_1") (pintype "passive"))
      (node (ref "J1") (pin "10") (pinfunction "10_10") (pintype "passive"))
      (node (ref "R472") (pin "2") (pinfunction "2_2") (pintype "passive"))
    )
    (net (code "95") (name "/OUT_P31") (class "Default")
      (node (ref "C229") (pin "1") (pinfunction "1_1") (pintype "passive"))
      (node (ref "J1") (pin "11") (pinfunction "11_11") (pintype "passive"))
      (node (ref "R450") (pin "2") (pinfunction "2_2") (pintype "passive"))
      (node (ref "R459") (pin "2") (pinfunction "2_2") (pintype "passive"))
    )
    (net (code "96") (name "/OUT_P32") (class "Default")
      (node (ref "C235") (pin "1") (pinfunction "1_1") (pintype "passive"))
      (node (ref "J1") (pin "9") (pinfunction "9_9") (pintype "passive"))
      (node (ref "R474") (pin "2") (pinfunction "2_2") (pintype "passive"))
    )
    (net (code "97") (name "/OUT_P33") (class "Default")
      (node (ref "C230") (pin "1") (pinfunction "1_1") (pintype "passive"))
      (node (ref "J10") (pin "36") (pinfunction "36_36") (pintype "passive"))
      (node (ref "R452") (pin "2") (pinfunction "2_2") (pintype "passive"))
      (node (ref "R460") (pin "2") (pinfunction "2_2") (pintype "passive"))
    )
    (net (code "98") (name "/OUT_P34") (class "Default")
      (node (ref "C236") (pin "1") (pinfunction "1_1") (pintype "passive"))
      (node (ref "J10") (pin "34") (pinfunction "34_34") (pintype "passive"))
      (node (ref "R476") (pin "2") (pinfunction "2_2") (pintype "passive"))
    )
    (net (code "99") (name "/OUT_P35") (class "Default")
      (node (ref "C231") (pin "1") (pinfunction "1_1") (pintype "passive"))
      (node (ref "J10") (pin "48") (pinfunction "48_48") (pintype "passive"))
      (node (ref "R454") (pin "2") (pinfunction "2_2") (pintype "passive"))
      (node (ref "R461") (pin "2") (pinfunction "2_2") (pintype "passive"))
    )
    (net (code "100") (name "/OUT_P36") (class "Default")
      (node (ref "C237") (pin "1") (pinfunction "1_1") (pintype "passive"))
      (node (ref "J10") (pin "46") (pinfunction "46_46") (pintype "passive"))
      (node (ref "R478") (pin "2") (pinfunction "2_2") (pintype "passive"))
    )
    (net (code "101") (name "/OUT_P37") (class "Default")
      (node (ref "C238") (pin "1") (pinfunction "1_1") (pintype "passive"))
      (node (ref "J1") (pin "41") (pinfunction "41_41") (pintype "passive"))
      (node (ref "R480") (pin "2") (pinfunction "2_2") (pintype "passive"))
      (node (ref "R492") (pin "2") (pinfunction "2_2") (pintype "passive"))
    )
    (net (code "102") (name "/OUT_P38") (class "Default")
      (node (ref "C244") (pin "1") (pinfunction "1_1") (pintype "passive"))
      (node (ref "J1") (pin "39") (pinfunction "39_39") (pintype "passive"))
      (node (ref "R504") (pin "2") (pinfunction "2_2") (pintype "passive"))
    )
    (net (code "103") (name "/OUT_P39") (class "Default")
      (node (ref "C239") (pin "1") (pinfunction "1_1") (pintype "passive"))
      (node (ref "J10") (pin "41") (pinfunction "41_41") (pintype "passive"))
      (node (ref "R482") (pin "2") (pinfunction "2_2") (pintype "passive"))
      (node (ref "R493") (pin "2") (pinfunction "2_2") (pintype "passive"))
    )
    (net (code "104") (name "/OUT_P40") (class "Default")
      (node (ref "C245") (pin "1") (pinfunction "1_1") (pintype "passive"))
      (node (ref "J10") (pin "39") (pinfunction "39_39") (pintype "passive"))
      (node (ref "R506") (pin "2") (pinfunction "2_2") (pintype "passive"))
    )
    (net (code "105") (name "/OUT_P41") (class "Default")
      (node (ref "C240") (pin "1") (pinfunction "1_1") (pintype "passive"))
      (node (ref "J1") (pin "29") (pinfunction "29_29") (pintype "passive"))
      (node (ref "R484") (pin "2") (pinfunction "2_2") (pintype "passive"))
      (node (ref "R494") (pin "2") (pinfunction "2_2") (pintype "passive"))
    )
    (net (code "106") (name "/OUT_P42") (class "Default")
      (node (ref "C246") (pin "1") (pinfunction "1_1") (pintype "passive"))
      (node (ref "J1") (pin "27") (pinfunction "27_27") (pintype "passive"))
      (node (ref "R508") (pin "2") (pinfunction "2_2") (pintype "passive"))
    )
    (net (code "107") (name "/OUT_P43") (class "Default")
      (node (ref "C241") (pin "1") (pinfunction "1_1") (pintype "passive"))
      (node (ref "J1") (pin "42") (pinfunction "42_42") (pintype "passive"))
      (node (ref "R486") (pin "2") (pinfunction "2_2") (pintype "passive"))
      (node (ref "R495") (pin "2") (pinfunction "2_2") (pintype "passive"))
    )
    (net (code "108") (name "/OUT_P44") (class "Default")
      (node (ref "C247") (pin "1") (pinfunction "1_1") (pintype "passive"))
      (node (ref "J1") (pin "40") (pinfunction "40_40") (pintype "passive"))
      (node (ref "R510") (pin "2") (pinfunction "2_2") (pintype "passive"))
    )
    (net (code "109") (name "/OUT_P45") (class "Default")
      (node (ref "C242") (pin "1") (pinfunction "1_1") (pintype "passive"))
      (node (ref "J10") (pin "47") (pinfunction "47_47") (pintype "passive"))
      (node (ref "R488") (pin "2") (pinfunction "2_2") (pintype "passive"))
      (node (ref "R496") (pin "2") (pinfunction "2_2") (pintype "passive"))
    )
    (net (code "110") (name "/OUT_P46") (class "Default")
      (node (ref "C248") (pin "1") (pinfunction "1_1") (pintype "passive"))
      (node (ref "J10") (pin "45") (pinfunction "45_45") (pintype "passive"))
      (node (ref "R512") (pin "2") (pinfunction "2_2") (pintype "passive"))
    )
    (net (code "111") (name "/OUT_P47") (class "Default")
      (node (ref "C243") (pin "1") (pinfunction "1_1") (pintype "passive"))
      (node (ref "J10") (pin "35") (pinfunction "35_35") (pintype "passive"))
      (node (ref "R490") (pin "2") (pinfunction "2_2") (pintype "passive"))
      (node (ref "R497") (pin "2") (pinfunction "2_2") (pintype "passive"))
    )
    (net (code "112") (name "/OUT_P48") (class "Default")
      (node (ref "C249") (pin "1") (pinfunction "1_1") (pintype "passive"))
      (node (ref "J10") (pin "33") (pinfunction "33_33") (pintype "passive"))
      (node (ref "R514") (pin "2") (pinfunction "2_2") (pintype "passive"))
    )
    (net (code "113") (name "/OUT_P49") (class "Default")
      (node (ref "C251") (pin "1") (pinfunction "1_1") (pintype "passive"))
      (node (ref "J1") (pin "30") (pinfunction "30_30") (pintype "passive"))
      (node (ref "R516") (pin "2") (pinfunction "2_2") (pintype "passive"))
      (node (ref "R528") (pin "2") (pinfunction "2_2") (pintype "passive"))
    )
    (net (code "114") (name "/OUT_P50") (class "Default")
      (node (ref "C257") (pin "1") (pinfunction "1_1") (pintype "passive"))
      (node (ref "J1") (pin "28") (pinfunction "28_28") (pintype "passive"))
      (node (ref "R540") (pin "2") (pinfunction "2_2") (pintype "passive"))
    )
    (net (code "115") (name "/OUT_P51") (class "Default")
      (node (ref "C252") (pin "1") (pinfunction "1_1") (pintype "passive"))
      (node (ref "J1") (pin "47") (pinfunction "47_47") (pintype "passive"))
      (node (ref "R518") (pin "2") (pinfunction "2_2") (pintype "passive"))
      (node (ref "R529") (pin "2") (pinfunction "2_2") (pintype "passive"))
    )
    (net (code "116") (name "/OUT_P52") (class "Default")
      (node (ref "C258") (pin "1") (pinfunction "1_1") (pintype "passive"))
      (node (ref "J1") (pin "45") (pinfunction "45_45") (pintype "passive"))
      (node (ref "R542") (pin "2") (pinfunction "2_2") (pintype "passive"))
    )
    (net (code "117") (name "/OUT_P53") (class "Default")
      (node (ref "C253") (pin "1") (pinfunction "1_1") (pintype "passive"))
      (node (ref "J1") (pin "36") (pinfunction "36_36") (pintype "passive"))
      (node (ref "R520") (pin "2") (pinfunction "2_2") (pintype "passive"))
      (node (ref "R530") (pin "2") (pinfunction "2_2") (pintype "passive"))
    )
    (net (code "118") (name "/OUT_P54") (class "Default")
      (node (ref "C259") (pin "1") (pinfunction "1_1") (pintype "passive"))
      (node (ref "J1") (pin "34") (pinfunction "34_34") (pintype "passive"))
      (node (ref "R544") (pin "2") (pinfunction "2_2") (pintype "passive"))
    )
    (net (code "119") (name "/OUT_P55") (class "Default")
      (node (ref "C254") (pin "1") (pinfunction "1_1") (pintype "passive"))
      (node (ref "J10") (pin "30") (pinfunction "30_30") (pintype "passive"))
      (node (ref "R522") (pin "2") (pinfunction "2_2") (pintype "passive"))
      (node (ref "R531") (pin "2") (pinfunction "2_2") (pintype "passive"))
    )
    (net (code "120") (name "/OUT_P56") (class "Default")
      (node (ref "C260") (pin "1") (pinfunction "1_1") (pintype "passive"))
      (node (ref "J10") (pin "28") (pinfunction "28_28") (pintype "passive"))
      (node (ref "R546") (pin "2") (pinfunction "2_2") (pintype "passive"))
    )
    (net (code "121") (name "/OUT_P57") (class "Default")
      (node (ref "C255") (pin "1") (pinfunction "1_1") (pintype "passive"))
      (node (ref "J1") (pin "48") (pinfunction "48_48") (pintype "passive"))
      (node (ref "R524") (pin "2") (pinfunction "2_2") (pintype "passive"))
      (node (ref "R532") (pin "2") (pinfunction "2_2") (pintype "passive"))
    )
    (net (code "122") (name "/OUT_P58") (class "Default")
      (node (ref "C261") (pin "1") (pinfunction "1_1") (pintype "passive"))
      (node (ref "J1") (pin "46") (pinfunction "46_46") (pintype "passive"))
      (node (ref "R548") (pin "2") (pinfunction "2_2") (pintype "passive"))
    )
    (net (code "123") (name "/OUT_P59") (class "Default")
      (node (ref "C256") (pin "1") (pinfunction "1_1") (pintype "passive"))
      (node (ref "J10") (pin "29") (pinfunction "29_29") (pintype "passive"))
      (node (ref "R526") (pin "2") (pinfunction "2_2") (pintype "passive"))
      (node (ref "R533") (pin "2") (pinfunction "2_2") (pintype "passive"))
    )
    (net (code "124") (name "/OUT_P60") (class "Default")
      (node (ref "C262") (pin "1") (pinfunction "1_1") (pintype "passive"))
      (node (ref "J10") (pin "27") (pinfunction "27_27") (pintype "passive"))
      (node (ref "R550") (pin "2") (pinfunction "2_2") (pintype "passive"))
    )
    (net (code "125") (name "/OUT_P61") (class "Default")
      (node (ref "C263") (pin "1") (pinfunction "1_1") (pintype "passive"))
      (node (ref "J1") (pin "35") (pinfunction "35_35") (pintype "passive"))
      (node (ref "R552") (pin "2") (pinfunction "2_2") (pintype "passive"))
      (node (ref "R556") (pin "2") (pinfunction "2_2") (pintype "passive"))
    )
    (net (code "126") (name "/OUT_P62") (class "Default")
      (node (ref "C265") (pin "1") (pinfunction "1_1") (pintype "passive"))
      (node (ref "J1") (pin "33") (pinfunction "33_33") (pintype "passive"))
      (node (ref "R560") (pin "2") (pinfunction "2_2") (pintype "passive"))
    )
    (net (code "127") (name "/OUT_P63") (class "Default")
      (node (ref "C264") (pin "1") (pinfunction "1_1") (pintype "passive"))
      (node (ref "J10") (pin "42") (pinfunction "42_42") (pintype "passive"))
      (node (ref "R554") (pin "2") (pinfunction "2_2") (pintype "passive"))
      (node (ref "R557") (pin "2") (pinfunction "2_2") (pintype "passive"))
    )
    (net (code "128") (name "/OUT_P64") (class "Default")
      (node (ref "C266") (pin "1") (pinfunction "1_1") (pintype "passive"))
      (node (ref "J10") (pin "40") (pinfunction "40_40") (pintype "passive"))
      (node (ref "R562") (pin "2") (pinfunction "2_2") (pintype "passive"))
    )
    (net (code "129") (name "GND") (class "Default")
      (node (ref "C151") (pin "2") (pinfunction "2_2") (pintype "passive"))
      (node (ref "C153") (pin "2") (pinfunction "2_2") (pintype "passive"))
      (node (ref "C155") (pin "2") (pinfunction "2_2") (pintype "passive"))
      (node (ref "C157") (pin "2") (pinfunction "2_2") (pintype "passive"))
      (node (ref "C176") (pin "2") (pinfunction "2_2") (pintype "passive"))
      (node (ref "C192") (pin "2") (pinfunction "2_2") (pintype "passive"))
      (node (ref "C206") (pin "2") (pinfunction "2_2") (pintype "passive"))
      (node (ref "C208") (pin "2") (pinfunction "2_2") (pintype "passive"))
      (node (ref "C209") (pin "2") (pinfunction "2_2") (pintype "passive"))
      (node (ref "C210") (pin "2") (pinfunction "2_2") (pintype "passive"))
      (node (ref "C214") (pin "2") (pinfunction "2_2") (pintype "passive"))
      (node (ref "C216") (pin "2") (pinfunction "2_2") (pintype "passive"))
      (node (ref "C217") (pin "2") (pinfunction "2_2") (pintype "passive"))
      (node (ref "C218") (pin "2") (pinfunction "2_2") (pintype "passive"))
      (node (ref "C219") (pin "2") (pinfunction "2_2") (pintype "passive"))
      (node (ref "C220") (pin "2") (pinfunction "2_2") (pintype "passive"))
      (node (ref "C221") (pin "2") (pinfunction "2_2") (pintype "passive"))
      (node (ref "C222") (pin "2") (pinfunction "2_2") (pintype "passive"))
      (node (ref "C223") (pin "2") (pinfunction "2_2") (pintype "passive"))
      (node (ref "C224") (pin "2") (pinfunction "2_2") (pintype "passive"))
      (node (ref "C225") (pin "2") (pinfunction "2_2") (pintype "passive"))
      (node (ref "C226") (pin "2") (pinfunction "2_2") (pintype "passive"))
      (node (ref "C227") (pin "2") (pinfunction "2_2") (pintype "passive"))
      (node (ref "C228") (pin "2") (pinfunction "2_2") (pintype "passive"))
      (node (ref "C229") (pin "2") (pinfunction "2_2") (pintype "passive"))
      (node (ref "C230") (pin "2") (pinfunction "2_2") (pintype "passive"))
      (node (ref "C231") (pin "2") (pinfunction "2_2") (pintype "passive"))
      (node (ref "C232") (pin "2") (pinfunction "2_2") (pintype "passive"))
      (node (ref "C233") (pin "2") (pinfunction "2_2") (pintype "passive"))
      (node (ref "C234") (pin "2") (pinfunction "2_2") (pintype "passive"))
      (node (ref "C235") (pin "2") (pinfunction "2_2") (pintype "passive"))
      (node (ref "C236") (pin "2") (pinfunction "2_2") (pintype "passive"))
      (node (ref "C237") (pin "2") (pinfunction "2_2") (pintype "passive"))
      (node (ref "C238") (pin "2") (pinfunction "2_2") (pintype "passive"))
      (node (ref "C239") (pin "2") (pinfunction "2_2") (pintype "passive"))
      (node (ref "C24") (pin "2") (pinfunction "2_2") (pintype "passive"))
      (node (ref "C240") (pin "2") (pinfunction "2_2") (pintype "passive"))
      (node (ref "C241") (pin "2") (pinfunction "2_2") (pintype "passive"))
      (node (ref "C242") (pin "2") (pinfunction "2_2") (pintype "passive"))
      (node (ref "C243") (pin "2") (pinfunction "2_2") (pintype "passive"))
      (node (ref "C244") (pin "2") (pinfunction "2_2") (pintype "passive"))
      (node (ref "C245") (pin "2") (pinfunction "2_2") (pintype "passive"))
      (node (ref "C246") (pin "2") (pinfunction "2_2") (pintype "passive"))
      (node (ref "C247") (pin "2") (pinfunction "2_2") (pintype "passive"))
      (node (ref "C248") (pin "2") (pinfunction "2_2") (pintype "passive"))
      (node (ref "C249") (pin "2") (pinfunction "2_2") (pintype "passive"))
      (node (ref "C251") (pin "2") (pinfunction "2_2") (pintype "passive"))
      (node (ref "C252") (pin "2") (pinfunction "2_2") (pintype "passive"))
      (node (ref "C253") (pin "2") (pinfunction "2_2") (pintype "passive"))
      (node (ref "C254") (pin "2") (pinfunction "2_2") (pintype "passive"))
      (node (ref "C255") (pin "2") (pinfunction "2_2") (pintype "passive"))
      (node (ref "C256") (pin "2") (pinfunction "2_2") (pintype "passive"))
      (node (ref "C257") (pin "2") (pinfunction "2_2") (pintype "passive"))
      (node (ref "C258") (pin "2") (pinfunction "2_2") (pintype "passive"))
      (node (ref "C259") (pin "2") (pinfunction "2_2") (pintype "passive"))
      (node (ref "C260") (pin "2") (pinfunction "2_2") (pintype "passive"))
      (node (ref "C261") (pin "2") (pinfunction "2_2") (pintype "passive"))
      (node (ref "C262") (pin "2") (pinfunction "2_2") (pintype "passive"))
      (node (ref "C263") (pin "2") (pinfunction "2_2") (pintype "passive"))
      (node (ref "C264") (pin "2") (pinfunction "2_2") (pintype "passive"))
      (node (ref "C265") (pin "2") (pinfunction "2_2") (pintype "passive"))
      (node (ref "C266") (pin "2") (pinfunction "2_2") (pintype "passive"))
      (node (ref "C70") (pin "2") (pinfunction "2_2") (pintype "passive"))
      (node (ref "C85") (pin "2") (pinfunction "2_2") (pintype "passive"))
      (node (ref "J1") (pin "1") (pinfunction "1_1") (pintype "passive"))
      (node (ref "J1") (pin "13") (pinfunction "13_13") (pintype "passive"))
      (node (ref "J1") (pin "14") (pinfunction "14_14") (pintype "passive"))
      (node (ref "J1") (pin "19") (pinfunction "19_19") (pintype "passive"))
      (node (ref "J1") (pin "2") (pinfunction "2_2") (pintype "passive"))
      (node (ref "J1") (pin "20") (pinfunction "20_20") (pintype "passive"))
      (node (ref "J1") (pin "25") (pinfunction "25_25") (pintype "passive"))
      (node (ref "J1") (pin "26") (pinfunction "26_26") (pintype "passive"))
      (node (ref "J1") (pin "31") (pinfunction "31_31") (pintype "passive"))
      (node (ref "J1") (pin "32") (pinfunction "32_32") (pintype "passive"))
      (node (ref "J1") (pin "37") (pinfunction "37_37") (pintype "passive"))
      (node (ref "J1") (pin "38") (pinfunction "38_38") (pintype "passive"))
      (node (ref "J1") (pin "43") (pinfunction "43_43") (pintype "passive"))
      (node (ref "J1") (pin "44") (pinfunction "44_44") (pintype "passive"))
      (node (ref "J1") (pin "49") (pinfunction "49_49") (pintype "passive"))
      (node (ref "J1") (pin "50") (pinfunction "50_50") (pintype "passive"))
      (node (ref "J1") (pin "7") (pinfunction "7_7") (pintype "passive"))
      (node (ref "J1") (pin "8") (pinfunction "8_8") (pintype "passive"))
      (node (ref "J10") (pin "1") (pinfunction "1_1") (pintype "passive"))
      (node (ref "J10") (pin "13") (pinfunction "13_13") (pintype "passive"))
      (node (ref "J10") (pin "14") (pinfunction "14_14") (pintype "passive"))
      (node (ref "J10") (pin "19") (pinfunction "19_19") (pintype "passive"))
      (node (ref "J10") (pin "2") (pinfunction "2_2") (pintype "passive"))
      (node (ref "J10") (pin "20") (pinfunction "20_20") (pintype "passive"))
      (node (ref "J10") (pin "25") (pinfunction "25_25") (pintype "passive"))
      (node (ref "J10") (pin "26") (pinfunction "26_26") (pintype "passive"))
      (node (ref "J10") (pin "31") (pinfunction "31_31") (pintype "passive"))
      (node (ref "J10") (pin "32") (pinfunction "32_32") (pintype "passive"))
      (node (ref "J10") (pin "37") (pinfunction "37_37") (pintype "passive"))
      (node (ref "J10") (pin "38") (pinfunction "38_38") (pintype "passive"))
      (node (ref "J10") (pin "43") (pinfunction "43_43") (pintype "passive"))
      (node (ref "J10") (pin "44") (pinfunction "44_44") (pintype "passive"))
      (node (ref "J10") (pin "49") (pinfunction "49_49") (pintype "passive"))
      (node (ref "J10") (pin "50") (pinfunction "50_50") (pintype "passive"))
      (node (ref "J10") (pin "7") (pinfunction "7_7") (pintype "passive"))
      (node (ref "J10") (pin "8") (pinfunction "8_8") (pintype "passive"))
      (node (ref "J14") (pin "2") (pinfunction "2_2") (pintype "passive"))
      (node (ref "J14") (pin "3") (pinfunction "3_3") (pintype "passive"))
      (node (ref "J14") (pin "4") (pinfunction "4_4") (pintype "passive"))
      (node (ref "J14") (pin "5") (pinfunction "5_5") (pintype "passive"))
      (node (ref "R375") (pin "1") (pinfunction "1_1") (pintype "passive"))
      (node (ref "R376") (pin "1") (pinfunction "1_1") (pintype "passive"))
      (node (ref "R377") (pin "1") (pinfunction "1_1") (pintype "passive"))
      (node (ref "R378") (pin "1") (pinfunction "1_1") (pintype "passive"))
      (node (ref "R379") (pin "1") (pinfunction "1_1") (pintype "passive"))
      (node (ref "R412") (pin "1") (pinfunction "1_1") (pintype "passive"))
      (node (ref "R413") (pin "1") (pinfunction "1_1") (pintype "passive"))
      (node (ref "R414") (pin "1") (pinfunction "1_1") (pintype "passive"))
      (node (ref "R415") (pin "1") (pinfunction "1_1") (pintype "passive"))
      (node (ref "R416") (pin "1") (pinfunction "1_1") (pintype "passive"))
      (node (ref "R417") (pin "1") (pinfunction "1_1") (pintype "passive"))
      (node (ref "R456") (pin "1") (pinfunction "1_1") (pintype "passive"))
      (node (ref "R457") (pin "1") (pinfunction "1_1") (pintype "passive"))
      (node (ref "R458") (pin "1") (pinfunction "1_1") (pintype "passive"))
      (node (ref "R459") (pin "1") (pinfunction "1_1") (pintype "passive"))
      (node (ref "R460") (pin "1") (pinfunction "1_1") (pintype "passive"))
      (node (ref "R461") (pin "1") (pinfunction "1_1") (pintype "passive"))
      (node (ref "R492") (pin "1") (pinfunction "1_1") (pintype "passive"))
      (node (ref "R493") (pin "1") (pinfunction "1_1") (pintype "passive"))
      (node (ref "R494") (pin "1") (pinfunction "1_1") (pintype "passive"))
      (node (ref "R495") (pin "1") (pinfunction "1_1") (pintype "passive"))
      (node (ref "R496") (pin "1") (pinfunction "1_1") (pintype "passive"))
      (node (ref "R497") (pin "1") (pinfunction "1_1") (pintype "passive"))
      (node (ref "R52") (pin "1") (pinfunction "1_1") (pintype "passive"))
      (node (ref "R528") (pin "1") (pinfunction "1_1") (pintype "passive"))
      (node (ref "R529") (pin "1") (pinfunction "1_1") (pintype "passive"))
      (node (ref "R530") (pin "1") (pinfunction "1_1") (pintype "passive"))
      (node (ref "R531") (pin "1") (pinfunction "1_1") (pintype "passive"))
      (node (ref "R532") (pin "1") (pinfunction "1_1") (pintype "passive"))
      (node (ref "R533") (pin "1") (pinfunction "1_1") (pintype "passive"))
      (node (ref "R556") (pin "1") (pinfunction "1_1") (pintype "passive"))
      (node (ref "R557") (pin "1") (pinfunction "1_1") (pintype "passive"))
      (node (ref "R565") (pin "1") (pinfunction "1_1") (pintype "passive"))
    )
    (net (code "130") (name "Net-(C267-Pad2)") (class "Default")
      (node (ref "C267") (pin "2") (pinfunction "2_2") (pintype "passive"))
      (node (ref "J14") (pin "1") (pinfunction "1_1") (pintype "passive"))
      (node (ref "R564") (pin "1") (pinfunction "1_1") (pintype "passive"))
      (node (ref "R565") (pin "2") (pinfunction "2_2") (pintype "passive"))
    )
  )
)
